# blinds_v60.net
KiCad netlist of a schematic drawn in EAGLE
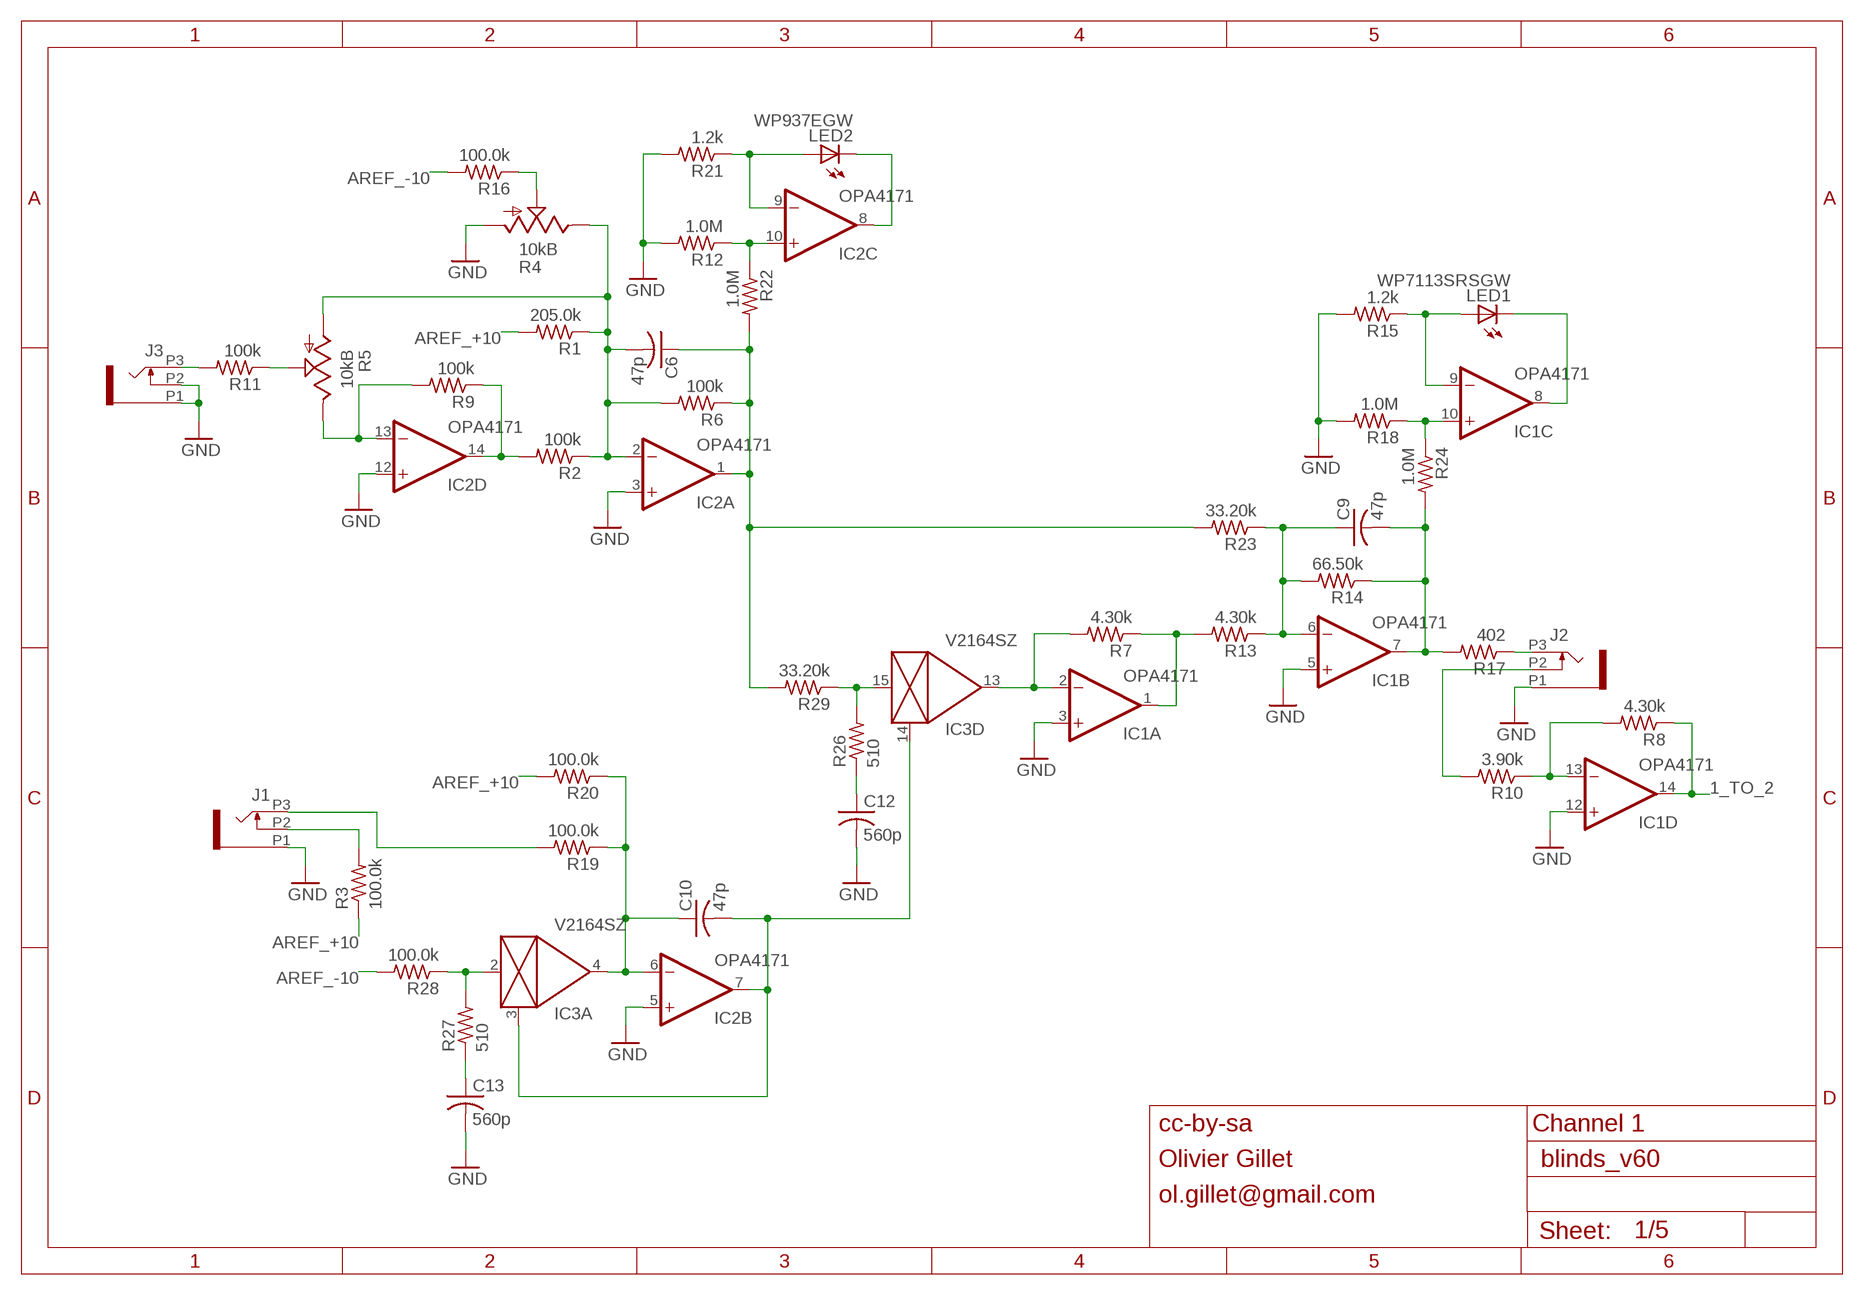
[diagram p0: schematic, sheet 1]
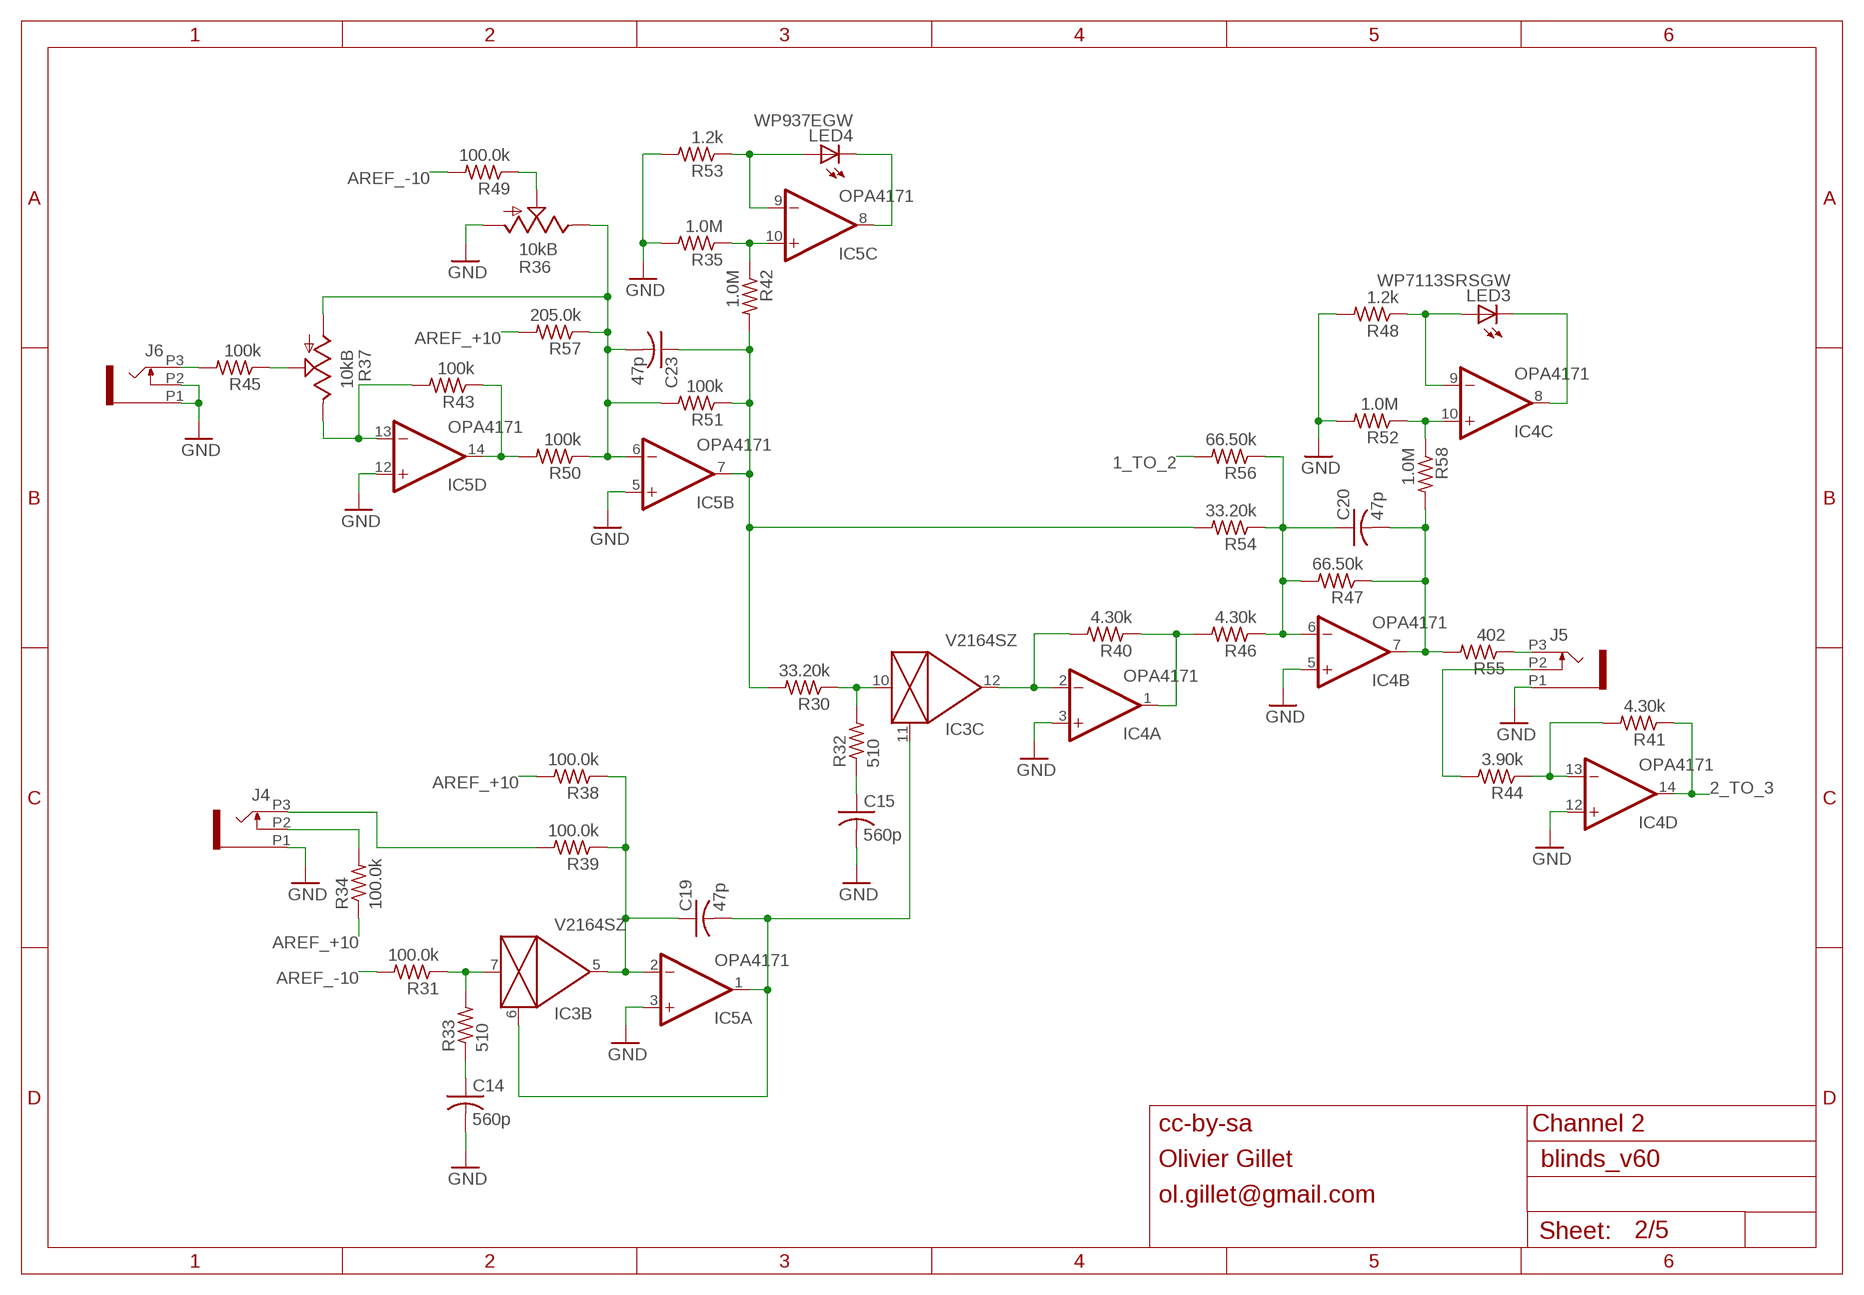
[diagram p1: schematic, sheet 2]
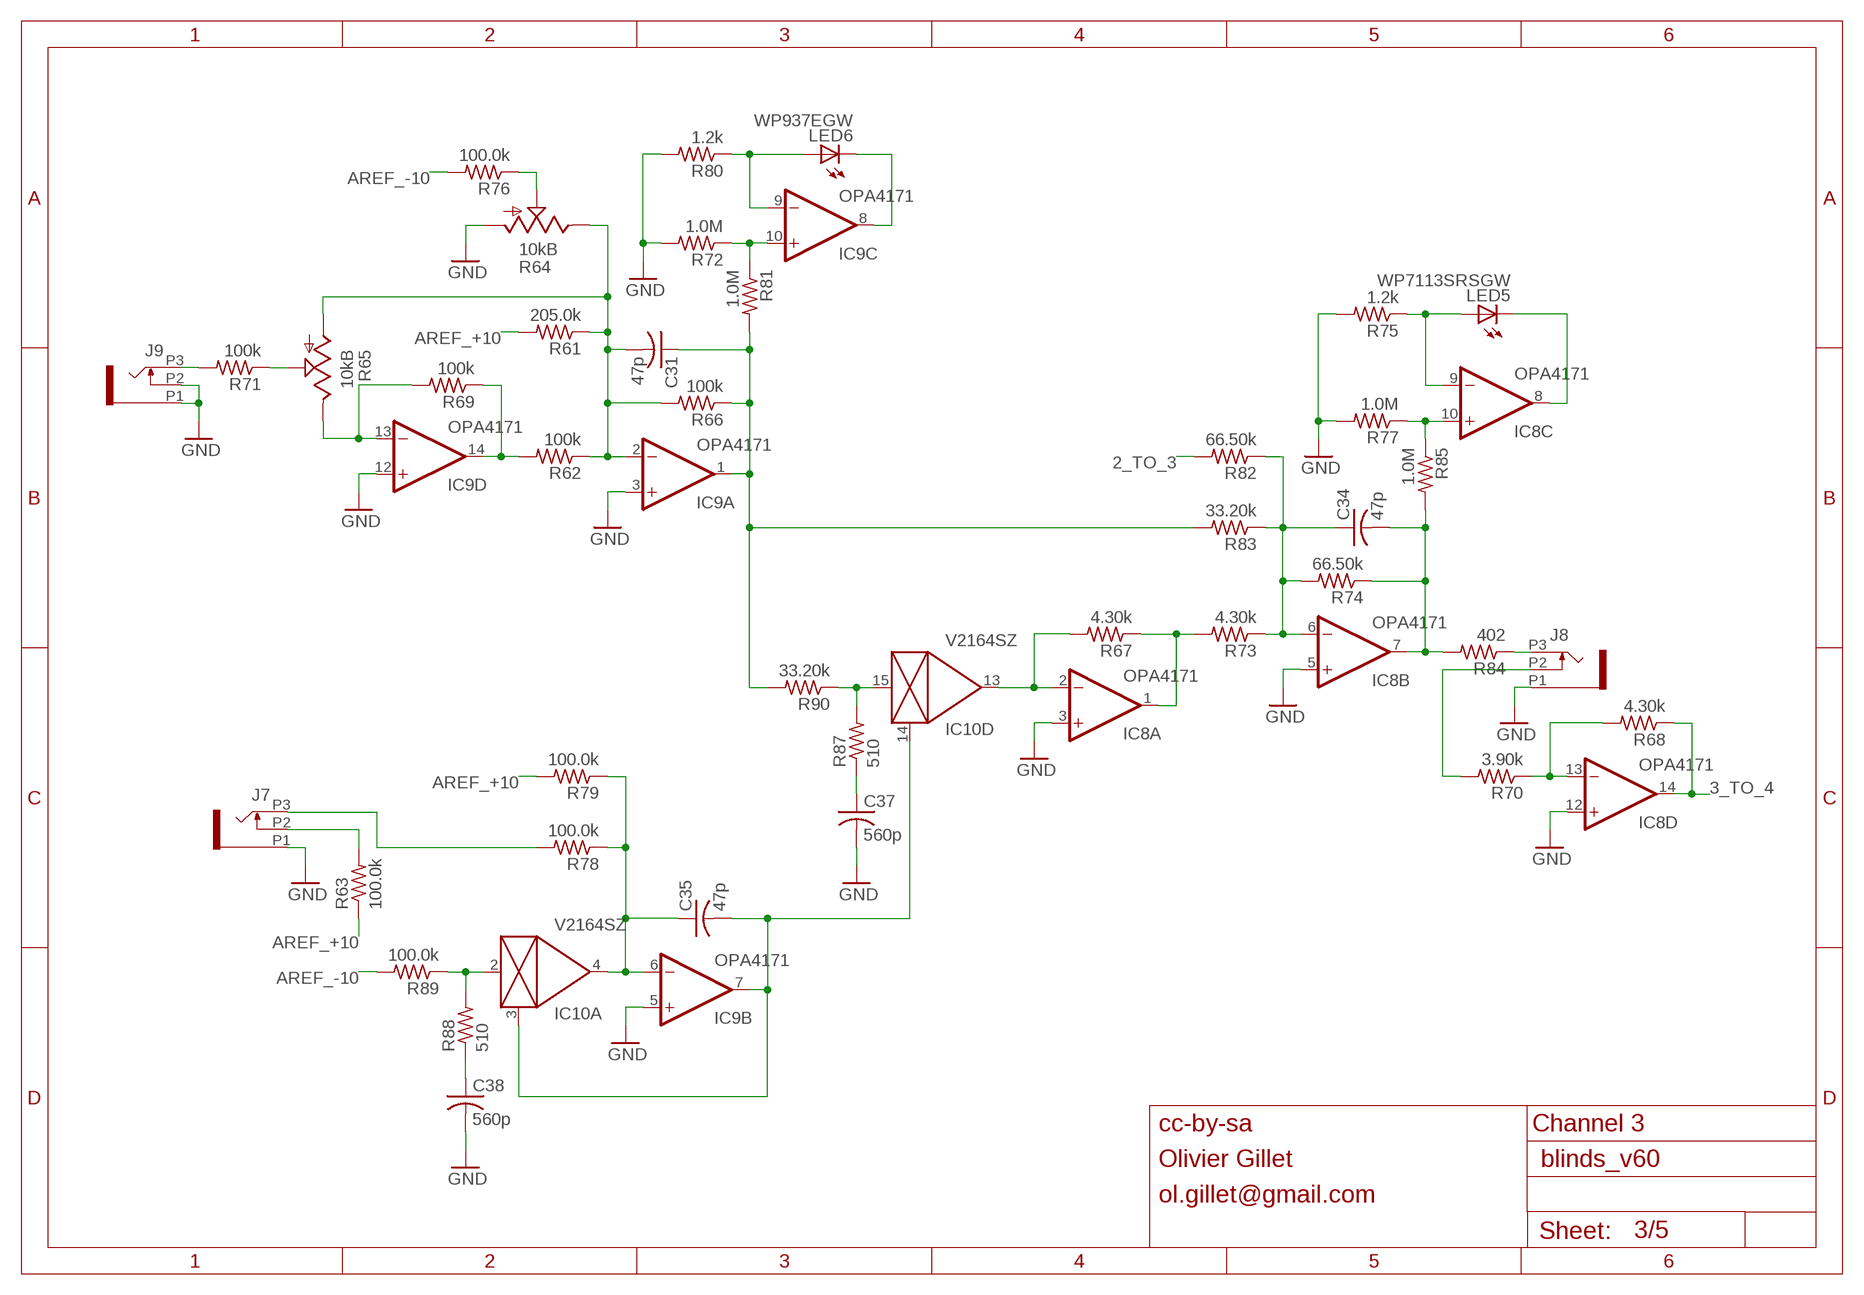
[diagram p2: schematic, sheet 3]
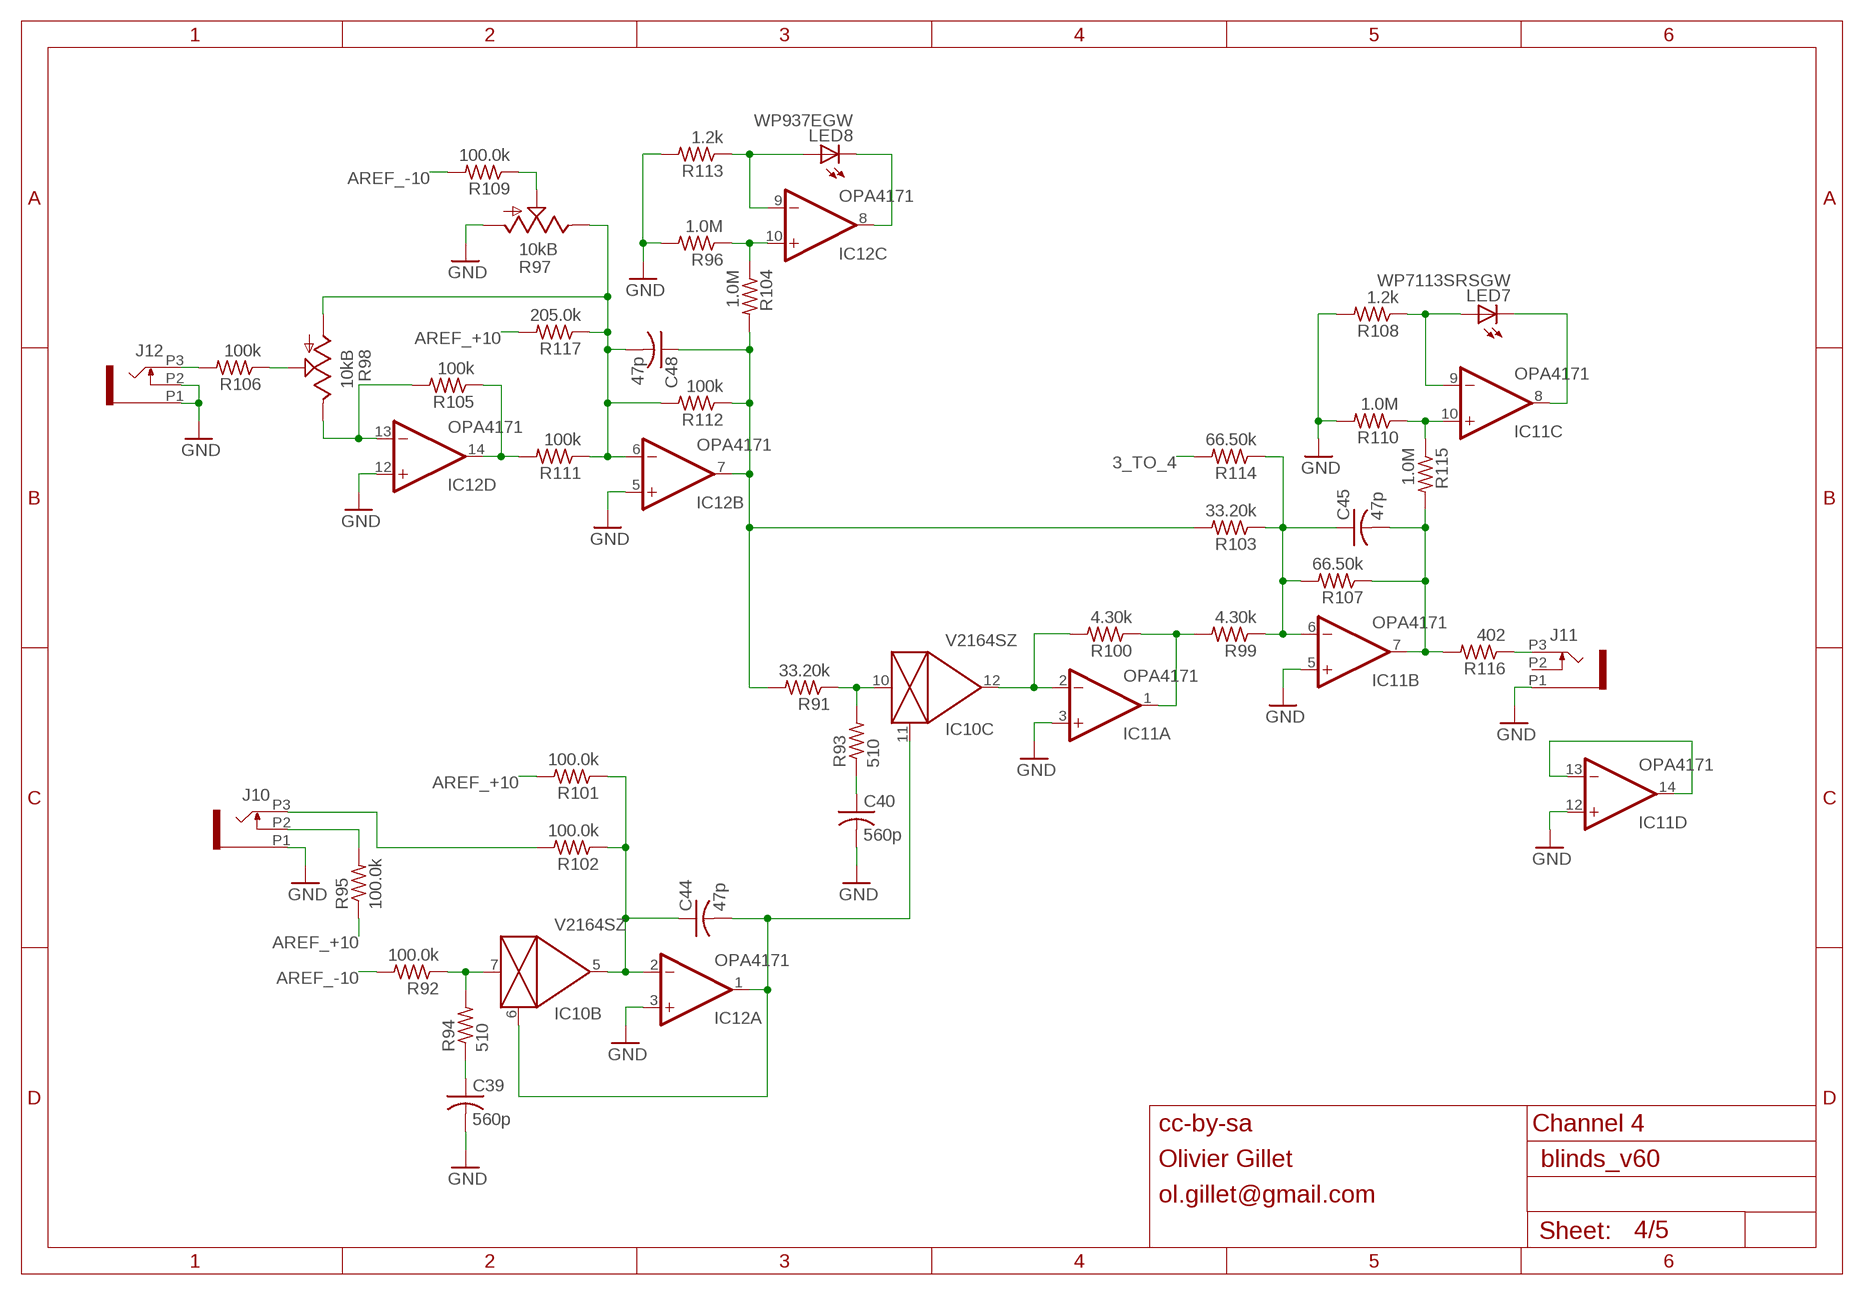
[diagram p3: schematic, sheet 4]
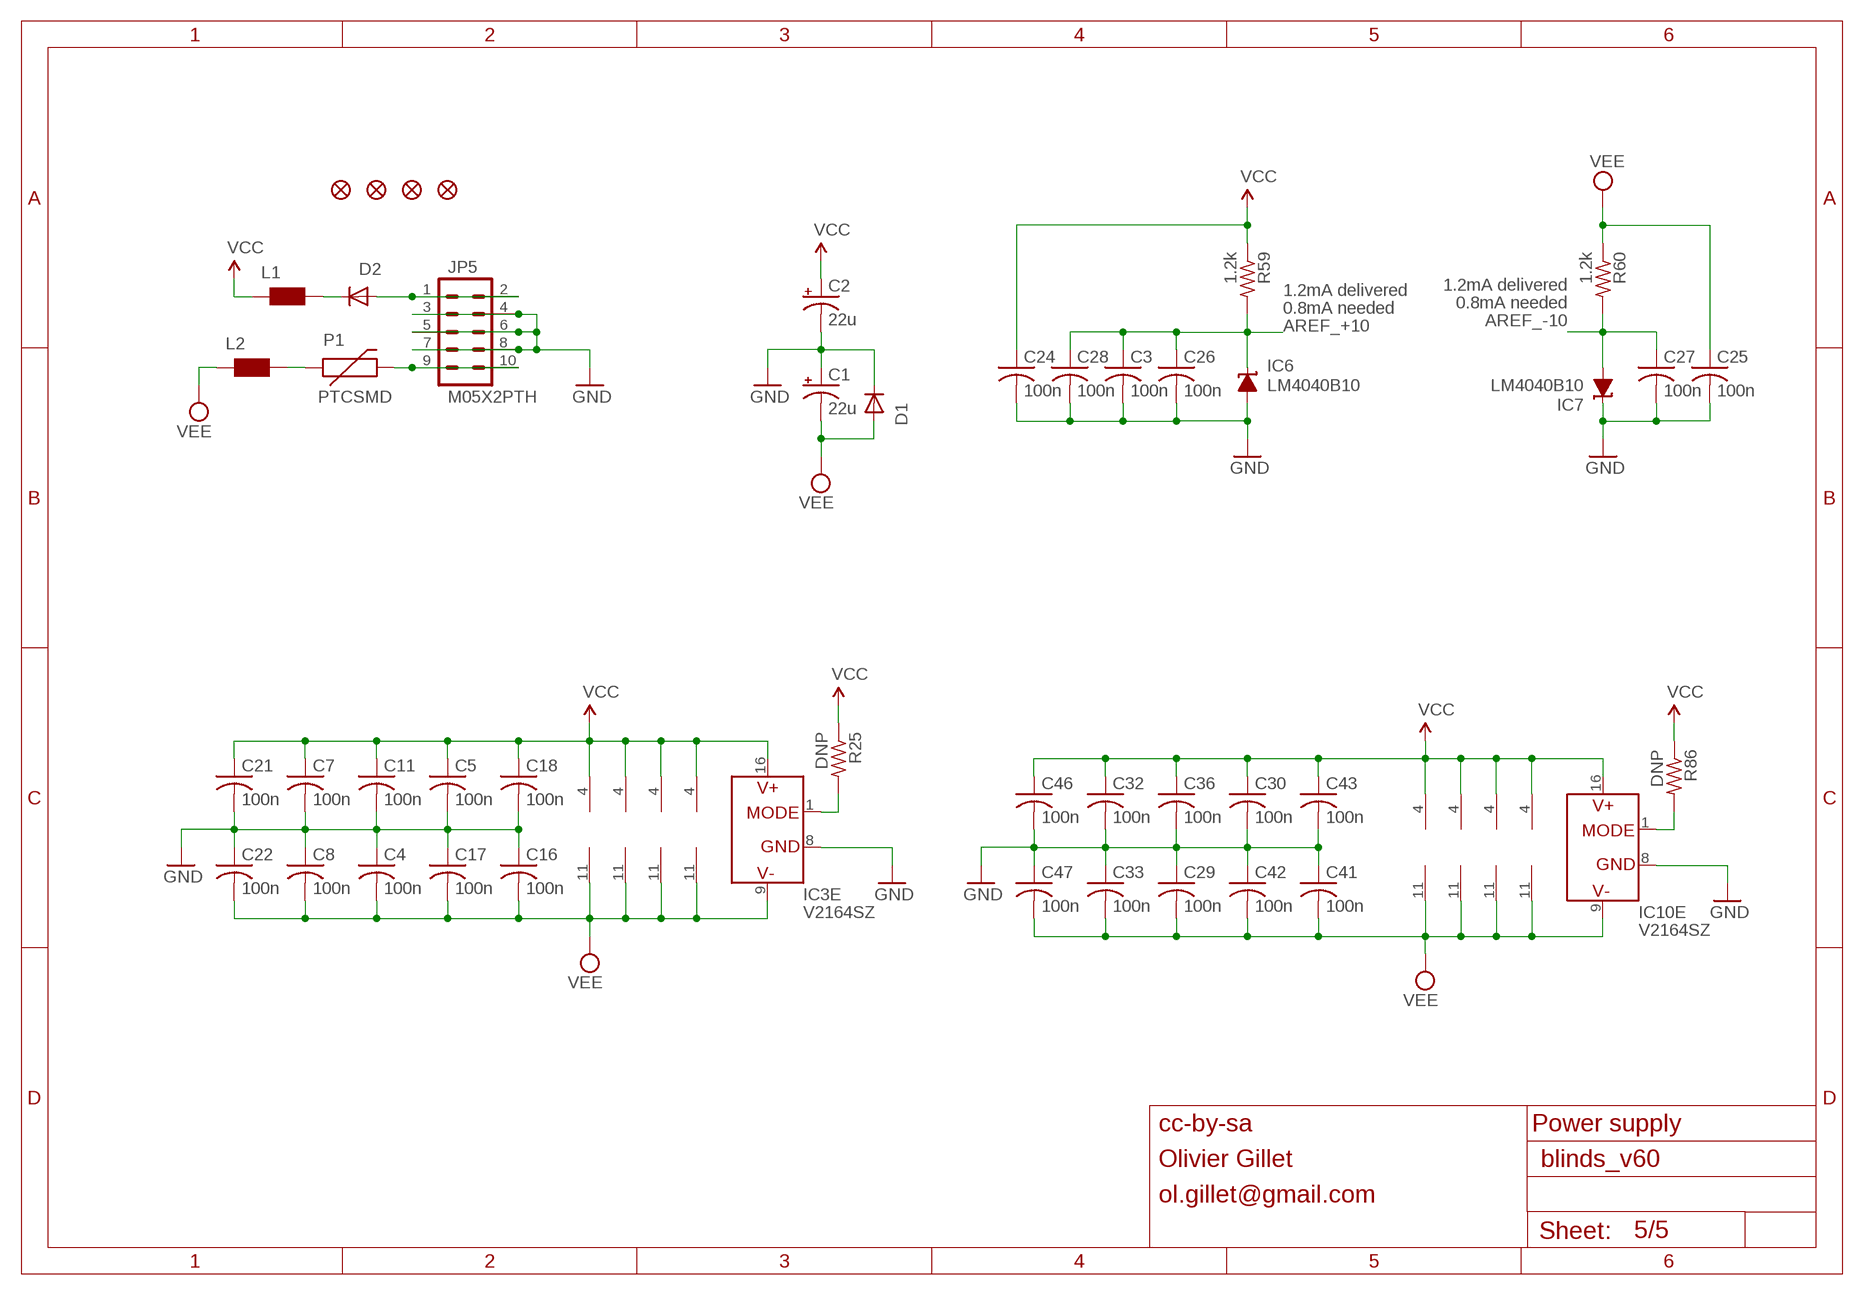
[diagram p4: schematic, sheet 5]

(export (version "E")
  (design (tool "Eeschema 10.0.6"))
  (components
    (comp (ref "C39")
      (value "560p")
      (footprint "eagle-import:C0603")
      (libsource (lib "eagle-import") (part "C-USC0603"))
    )
    (comp (ref "C40")
      (value "560p")
      (footprint "eagle-import:C0603")
      (libsource (lib "eagle-import") (part "C-USC0603"))
    )
    (comp (ref "C44")
      (value "47p")
      (footprint "eagle-import:C0603")
      (libsource (lib "eagle-import") (part "C-USC0603"))
    )
    (comp (ref "C45")
      (value "47p")
      (footprint "eagle-import:C0603")
      (libsource (lib "eagle-import") (part "C-USC0603"))
    )
    (comp (ref "C48")
      (value "47p")
      (footprint "eagle-import:C0603")
      (libsource (lib "eagle-import") (part "C-USC0603"))
    )
    (comp (ref "IC10")
      (value "V2164SZ")
      (footprint "eagle-import:SOIC16N")
      (libsource (lib "eagle-import") (part "SSM2164S"))
    )
    (comp (ref "IC11")
      (value "OPA4171")
      (footprint "eagle-import:TSSOP14")
      (libsource (lib "eagle-import") (part "TL074PW"))
    )
    (comp (ref "IC12")
      (value "OPA4171")
      (footprint "eagle-import:TSSOP14")
      (libsource (lib "eagle-import") (part "TL074PW"))
    )
    (comp (ref "J10")
      (value "PJ301_THONKICONN6")
      (footprint "eagle-import:WQP_PJ_301M6")
      (libsource (lib "eagle-import") (part "PJ301_THONKICONN6"))
    )
    (comp (ref "J11")
      (value "PJ301_THONKICONN6")
      (footprint "eagle-import:WQP_PJ_301M6")
      (libsource (lib "eagle-import") (part "PJ301_THONKICONN6"))
    )
    (comp (ref "J12")
      (value "PJ301_THONKICONN6")
      (footprint "eagle-import:WQP_PJ_301M6")
      (libsource (lib "eagle-import") (part "PJ301_THONKICONN6"))
    )
    (comp (ref "LED7")
      (value "WP7113SRSGW")
      (footprint "eagle-import:LED5MM")
      (libsource (lib "eagle-import") (part "LED5MM"))
    )
    (comp (ref "LED8")
      (value "WP937EGW")
      (footprint "eagle-import:LED3MM")
      (libsource (lib "eagle-import") (part "LED3MM"))
    )
    (comp (ref "R91")
      (value "33.20k")
      (footprint "eagle-import:R0603")
      (libsource (lib "eagle-import") (part "R-US_R0603"))
    )
    (comp (ref "R92")
      (value "100.0k")
      (footprint "eagle-import:R0603")
      (libsource (lib "eagle-import") (part "R-US_R0603"))
    )
    (comp (ref "R93")
      (value "510")
      (footprint "eagle-import:R0603")
      (libsource (lib "eagle-import") (part "R-US_R0603"))
    )
    (comp (ref "R94")
      (value "510")
      (footprint "eagle-import:R0603")
      (libsource (lib "eagle-import") (part "R-US_R0603"))
    )
    (comp (ref "R95")
      (value "100.0k")
      (footprint "eagle-import:R0603")
      (libsource (lib "eagle-import") (part "R-US_R0603"))
    )
    (comp (ref "R96")
      (value "1.0M")
      (footprint "eagle-import:R0603")
      (libsource (lib "eagle-import") (part "R-US_R0603"))
    )
    (comp (ref "R97")
      (value "10kB")
      (footprint "eagle-import:ALPS_POT_VERTICAL_PS")
      (libsource (lib "eagle-import") (part "POT_USVERTICAL_PS"))
    )
    (comp (ref "R98")
      (value "10kB")
      (footprint "eagle-import:ALPS_POT_VERTICAL")
      (libsource (lib "eagle-import") (part "POT_USVERTICAL"))
    )
    (comp (ref "R99")
      (value "4.30k")
      (footprint "eagle-import:R0603")
      (libsource (lib "eagle-import") (part "R-US_R0603"))
    )
    (comp (ref "R100")
      (value "4.30k")
      (footprint "eagle-import:R0603")
      (libsource (lib "eagle-import") (part "R-US_R0603"))
    )
    (comp (ref "R101")
      (value "100.0k")
      (footprint "eagle-import:R0603")
      (libsource (lib "eagle-import") (part "R-US_R0603"))
    )
    (comp (ref "R102")
      (value "100.0k")
      (footprint "eagle-import:R0603")
      (libsource (lib "eagle-import") (part "R-US_R0603"))
    )
    (comp (ref "R103")
      (value "33.20k")
      (footprint "eagle-import:R0603")
      (libsource (lib "eagle-import") (part "R-US_R0603"))
    )
    (comp (ref "R104")
      (value "1.0M")
      (footprint "eagle-import:R0603")
      (libsource (lib "eagle-import") (part "R-US_R0603"))
    )
    (comp (ref "R105")
      (value "100k")
      (footprint "eagle-import:R0603")
      (libsource (lib "eagle-import") (part "R-US_R0603"))
    )
    (comp (ref "R106")
      (value "100k")
      (footprint "eagle-import:R0603")
      (libsource (lib "eagle-import") (part "R-US_R0603"))
    )
    (comp (ref "R107")
      (value "66.50k")
      (footprint "eagle-import:R0603")
      (libsource (lib "eagle-import") (part "R-US_R0603"))
    )
    (comp (ref "R108")
      (value "1.2k")
      (footprint "eagle-import:R0603")
      (libsource (lib "eagle-import") (part "R-US_R0603"))
    )
    (comp (ref "R109")
      (value "100.0k")
      (footprint "eagle-import:R0603")
      (libsource (lib "eagle-import") (part "R-US_R0603"))
    )
    (comp (ref "R110")
      (value "1.0M")
      (footprint "eagle-import:R0603")
      (libsource (lib "eagle-import") (part "R-US_R0603"))
    )
    (comp (ref "R111")
      (value "100k")
      (footprint "eagle-import:R0603")
      (libsource (lib "eagle-import") (part "R-US_R0603"))
    )
    (comp (ref "R112")
      (value "100k")
      (footprint "eagle-import:R0603")
      (libsource (lib "eagle-import") (part "R-US_R0603"))
    )
    (comp (ref "R113")
      (value "1.2k")
      (footprint "eagle-import:R0603")
      (libsource (lib "eagle-import") (part "R-US_R0603"))
    )
    (comp (ref "R114")
      (value "66.50k")
      (footprint "eagle-import:R0603")
      (libsource (lib "eagle-import") (part "R-US_R0603"))
    )
    (comp (ref "R115")
      (value "1.0M")
      (footprint "eagle-import:R0603")
      (libsource (lib "eagle-import") (part "R-US_R0603"))
    )
    (comp (ref "R116")
      (value "402")
      (footprint "eagle-import:R0603")
      (libsource (lib "eagle-import") (part "R-US_R0603"))
    )
    (comp (ref "R117")
      (value "205.0k")
      (footprint "eagle-import:R0603")
      (libsource (lib "eagle-import") (part "R-US_R0603"))
    )
    (comp (ref "C1")
      (value "22u")
      (footprint "eagle-import:PANASONIC_C")
      (libsource (lib "eagle-import") (part "CPOL-USC"))
    )
    (comp (ref "C2")
      (value "22u")
      (footprint "eagle-import:PANASONIC_C")
      (libsource (lib "eagle-import") (part "CPOL-USC"))
    )
    (comp (ref "C3")
      (value "100n")
      (footprint "eagle-import:C0603")
      (libsource (lib "eagle-import") (part "C-USC0603"))
    )
    (comp (ref "C4")
      (value "100n")
      (footprint "eagle-import:C0603")
      (libsource (lib "eagle-import") (part "C-USC0603"))
    )
    (comp (ref "C5")
      (value "100n")
      (footprint "eagle-import:C0603")
      (libsource (lib "eagle-import") (part "C-USC0603"))
    )
    (comp (ref "C7")
      (value "100n")
      (footprint "eagle-import:C0603")
      (libsource (lib "eagle-import") (part "C-USC0603"))
    )
    (comp (ref "C8")
      (value "100n")
      (footprint "eagle-import:C0603")
      (libsource (lib "eagle-import") (part "C-USC0603"))
    )
    (comp (ref "C11")
      (value "100n")
      (footprint "eagle-import:C0603")
      (libsource (lib "eagle-import") (part "C-USC0603"))
    )
    (comp (ref "C16")
      (value "100n")
      (footprint "eagle-import:C0603")
      (libsource (lib "eagle-import") (part "C-USC0603"))
    )
    (comp (ref "C17")
      (value "100n")
      (footprint "eagle-import:C0603")
      (libsource (lib "eagle-import") (part "C-USC0603"))
    )
    (comp (ref "C18")
      (value "100n")
      (footprint "eagle-import:C0603")
      (libsource (lib "eagle-import") (part "C-USC0603"))
    )
    (comp (ref "C21")
      (value "100n")
      (footprint "eagle-import:C0603")
      (libsource (lib "eagle-import") (part "C-USC0603"))
    )
    (comp (ref "C22")
      (value "100n")
      (footprint "eagle-import:C0603")
      (libsource (lib "eagle-import") (part "C-USC0603"))
    )
    (comp (ref "C24")
      (value "100n")
      (footprint "eagle-import:C0603")
      (libsource (lib "eagle-import") (part "C-USC0603"))
    )
    (comp (ref "C25")
      (value "100n")
      (footprint "eagle-import:C0603")
      (libsource (lib "eagle-import") (part "C-USC0603"))
    )
    (comp (ref "C26")
      (value "100n")
      (footprint "eagle-import:C0603")
      (libsource (lib "eagle-import") (part "C-USC0603"))
    )
    (comp (ref "C27")
      (value "100n")
      (footprint "eagle-import:C0603")
      (libsource (lib "eagle-import") (part "C-USC0603"))
    )
    (comp (ref "C28")
      (value "100n")
      (footprint "eagle-import:C0603")
      (libsource (lib "eagle-import") (part "C-USC0603"))
    )
    (comp (ref "C29")
      (value "100n")
      (footprint "eagle-import:C0603")
      (libsource (lib "eagle-import") (part "C-USC0603"))
    )
    (comp (ref "C30")
      (value "100n")
      (footprint "eagle-import:C0603")
      (libsource (lib "eagle-import") (part "C-USC0603"))
    )
    (comp (ref "C32")
      (value "100n")
      (footprint "eagle-import:C0603")
      (libsource (lib "eagle-import") (part "C-USC0603"))
    )
    (comp (ref "C33")
      (value "100n")
      (footprint "eagle-import:C0603")
      (libsource (lib "eagle-import") (part "C-USC0603"))
    )
    (comp (ref "C36")
      (value "100n")
      (footprint "eagle-import:C0603")
      (libsource (lib "eagle-import") (part "C-USC0603"))
    )
    (comp (ref "C41")
      (value "100n")
      (footprint "eagle-import:C0603")
      (libsource (lib "eagle-import") (part "C-USC0603"))
    )
    (comp (ref "C42")
      (value "100n")
      (footprint "eagle-import:C0603")
      (libsource (lib "eagle-import") (part "C-USC0603"))
    )
    (comp (ref "C43")
      (value "100n")
      (footprint "eagle-import:C0603")
      (libsource (lib "eagle-import") (part "C-USC0603"))
    )
    (comp (ref "C46")
      (value "100n")
      (footprint "eagle-import:C0603")
      (libsource (lib "eagle-import") (part "C-USC0603"))
    )
    (comp (ref "C47")
      (value "100n")
      (footprint "eagle-import:C0603")
      (libsource (lib "eagle-import") (part "C-USC0603"))
    )
    (comp (ref "D1")
      (value "1N5819HW")
      (footprint "eagle-import:SOD123")
      (libsource (lib "eagle-import") (part "DIODE-SOD123"))
    )
    (comp (ref "D2")
      (value "1N5819HW")
      (footprint "eagle-import:SOD123")
      (libsource (lib "eagle-import") (part "DIODE-SOD123"))
    )
    (comp (ref "IC1")
      (value "OPA4171")
      (footprint "eagle-import:TSSOP14")
      (libsource (lib "eagle-import") (part "TL074PW"))
    )
    (comp (ref "IC2")
      (value "OPA4171")
      (footprint "eagle-import:TSSOP14")
      (libsource (lib "eagle-import") (part "TL074PW"))
    )
    (comp (ref "IC3")
      (value "V2164SZ")
      (footprint "eagle-import:SOIC16N")
      (libsource (lib "eagle-import") (part "SSM2164S"))
    )
    (comp (ref "IC4")
      (value "OPA4171")
      (footprint "eagle-import:TSSOP14")
      (libsource (lib "eagle-import") (part "TL074PW"))
    )
    (comp (ref "IC5")
      (value "OPA4171")
      (footprint "eagle-import:TSSOP14")
      (libsource (lib "eagle-import") (part "TL074PW"))
    )
    (comp (ref "IC6")
      (value "LM4040B10")
      (footprint "eagle-import:DBZ_R-PDSO-G3")
      (libsource (lib "eagle-import") (part "LM4041DBZB12"))
    )
    (comp (ref "IC7")
      (value "LM4040B10")
      (footprint "eagle-import:DBZ_R-PDSO-G3")
      (libsource (lib "eagle-import") (part "LM4041DBZB12"))
    )
    (comp (ref "IC8")
      (value "OPA4171")
      (footprint "eagle-import:TSSOP14")
      (libsource (lib "eagle-import") (part "TL074PW"))
    )
    (comp (ref "IC9")
      (value "OPA4171")
      (footprint "eagle-import:TSSOP14")
      (libsource (lib "eagle-import") (part "TL074PW"))
    )
    (comp (ref "JP1")
      (value "FIDUCIAL1X2")
      (footprint "eagle-import:FIDUCIAL-1X2")
      (libsource (lib "eagle-import") (part "FIDUCIAL1X2"))
    )
    (comp (ref "JP2")
      (value "FIDUCIAL1X2")
      (footprint "eagle-import:FIDUCIAL-1X2")
      (libsource (lib "eagle-import") (part "FIDUCIAL1X2"))
    )
    (comp (ref "JP3")
      (value "FIDUCIAL1X2")
      (footprint "eagle-import:FIDUCIAL-1X2")
      (libsource (lib "eagle-import") (part "FIDUCIAL1X2"))
    )
    (comp (ref "JP4")
      (value "FIDUCIAL1X2")
      (footprint "eagle-import:FIDUCIAL-1X2")
      (libsource (lib "eagle-import") (part "FIDUCIAL1X2"))
    )
    (comp (ref "JP5")
      (value "M05X2PTH")
      (footprint "eagle-import:AVR_ICSP")
      (libsource (lib "eagle-import") (part "M05X2PTH"))
    )
    (comp (ref "L1")
      (value "WE-CBF_0603")
      (footprint "eagle-import:0603")
      (libsource (lib "eagle-import") (part "WE-CBF_0603"))
    )
    (comp (ref "L2")
      (value "WE-CBF_0603")
      (footprint "eagle-import:0603")
      (libsource (lib "eagle-import") (part "WE-CBF_0603"))
    )
    (comp (ref "P1")
      (value "PTCSMD")
      (footprint "eagle-import:PTC-1206")
      (libsource (lib "eagle-import") (part "PTCSMD"))
    )
    (comp (ref "R25")
      (value "DNP")
      (footprint "eagle-import:R0603")
      (libsource (lib "eagle-import") (part "R-US_R0603"))
    )
    (comp (ref "R59")
      (value "1.2k")
      (footprint "eagle-import:R0603")
      (libsource (lib "eagle-import") (part "R-US_R0603"))
    )
    (comp (ref "R60")
      (value "1.2k")
      (footprint "eagle-import:R0603")
      (libsource (lib "eagle-import") (part "R-US_R0603"))
    )
    (comp (ref "R86")
      (value "DNP")
      (footprint "eagle-import:R0603")
      (libsource (lib "eagle-import") (part "R-US_R0603"))
    )
    (comp (ref "C14")
      (value "560p")
      (footprint "eagle-import:C0603")
      (libsource (lib "eagle-import") (part "C-USC0603"))
    )
    (comp (ref "C15")
      (value "560p")
      (footprint "eagle-import:C0603")
      (libsource (lib "eagle-import") (part "C-USC0603"))
    )
    (comp (ref "C19")
      (value "47p")
      (footprint "eagle-import:C0603")
      (libsource (lib "eagle-import") (part "C-USC0603"))
    )
    (comp (ref "C20")
      (value "47p")
      (footprint "eagle-import:C0603")
      (libsource (lib "eagle-import") (part "C-USC0603"))
    )
    (comp (ref "C23")
      (value "47p")
      (footprint "eagle-import:C0603")
      (libsource (lib "eagle-import") (part "C-USC0603"))
    )
    (comp (ref "J4")
      (value "PJ301_THONKICONN6")
      (footprint "eagle-import:WQP_PJ_301M6")
      (libsource (lib "eagle-import") (part "PJ301_THONKICONN6"))
    )
    (comp (ref "J5")
      (value "PJ301_THONKICONN6")
      (footprint "eagle-import:WQP_PJ_301M6")
      (libsource (lib "eagle-import") (part "PJ301_THONKICONN6"))
    )
    (comp (ref "J6")
      (value "PJ301_THONKICONN6")
      (footprint "eagle-import:WQP_PJ_301M6")
      (libsource (lib "eagle-import") (part "PJ301_THONKICONN6"))
    )
    (comp (ref "LED3")
      (value "WP7113SRSGW")
      (footprint "eagle-import:LED5MM")
      (libsource (lib "eagle-import") (part "LED5MM"))
    )
    (comp (ref "LED4")
      (value "WP937EGW")
      (footprint "eagle-import:LED3MM")
      (libsource (lib "eagle-import") (part "LED3MM"))
    )
    (comp (ref "R30")
      (value "33.20k")
      (footprint "eagle-import:R0603")
      (libsource (lib "eagle-import") (part "R-US_R0603"))
    )
    (comp (ref "R31")
      (value "100.0k")
      (footprint "eagle-import:R0603")
      (libsource (lib "eagle-import") (part "R-US_R0603"))
    )
    (comp (ref "R32")
      (value "510")
      (footprint "eagle-import:R0603")
      (libsource (lib "eagle-import") (part "R-US_R0603"))
    )
    (comp (ref "R33")
      (value "510")
      (footprint "eagle-import:R0603")
      (libsource (lib "eagle-import") (part "R-US_R0603"))
    )
    (comp (ref "R34")
      (value "100.0k")
      (footprint "eagle-import:R0603")
      (libsource (lib "eagle-import") (part "R-US_R0603"))
    )
    (comp (ref "R35")
      (value "1.0M")
      (footprint "eagle-import:R0603")
      (libsource (lib "eagle-import") (part "R-US_R0603"))
    )
    (comp (ref "R36")
      (value "10kB")
      (footprint "eagle-import:ALPS_POT_VERTICAL_PS")
      (libsource (lib "eagle-import") (part "POT_USVERTICAL_PS"))
    )
    (comp (ref "R37")
      (value "10kB")
      (footprint "eagle-import:ALPS_POT_VERTICAL")
      (libsource (lib "eagle-import") (part "POT_USVERTICAL"))
    )
    (comp (ref "R38")
      (value "100.0k")
      (footprint "eagle-import:R0603")
      (libsource (lib "eagle-import") (part "R-US_R0603"))
    )
    (comp (ref "R39")
      (value "100.0k")
      (footprint "eagle-import:R0603")
      (libsource (lib "eagle-import") (part "R-US_R0603"))
    )
    (comp (ref "R40")
      (value "4.30k")
      (footprint "eagle-import:R0603")
      (libsource (lib "eagle-import") (part "R-US_R0603"))
    )
    (comp (ref "R41")
      (value "4.30k")
      (footprint "eagle-import:R0603")
      (libsource (lib "eagle-import") (part "R-US_R0603"))
    )
    (comp (ref "R42")
      (value "1.0M")
      (footprint "eagle-import:R0603")
      (libsource (lib "eagle-import") (part "R-US_R0603"))
    )
    (comp (ref "R43")
      (value "100k")
      (footprint "eagle-import:R0603")
      (libsource (lib "eagle-import") (part "R-US_R0603"))
    )
    (comp (ref "R44")
      (value "3.90k")
      (footprint "eagle-import:R0603")
      (libsource (lib "eagle-import") (part "R-US_R0603"))
    )
    (comp (ref "R45")
      (value "100k")
      (footprint "eagle-import:R0603")
      (libsource (lib "eagle-import") (part "R-US_R0603"))
    )
    (comp (ref "R46")
      (value "4.30k")
      (footprint "eagle-import:R0603")
      (libsource (lib "eagle-import") (part "R-US_R0603"))
    )
    (comp (ref "R47")
      (value "66.50k")
      (footprint "eagle-import:R0603")
      (libsource (lib "eagle-import") (part "R-US_R0603"))
    )
    (comp (ref "R48")
      (value "1.2k")
      (footprint "eagle-import:R0603")
      (libsource (lib "eagle-import") (part "R-US_R0603"))
    )
    (comp (ref "R49")
      (value "100.0k")
      (footprint "eagle-import:R0603")
      (libsource (lib "eagle-import") (part "R-US_R0603"))
    )
    (comp (ref "R50")
      (value "100k")
      (footprint "eagle-import:R0603")
      (libsource (lib "eagle-import") (part "R-US_R0603"))
    )
    (comp (ref "R51")
      (value "100k")
      (footprint "eagle-import:R0603")
      (libsource (lib "eagle-import") (part "R-US_R0603"))
    )
    (comp (ref "R52")
      (value "1.0M")
      (footprint "eagle-import:R0603")
      (libsource (lib "eagle-import") (part "R-US_R0603"))
    )
    (comp (ref "R53")
      (value "1.2k")
      (footprint "eagle-import:R0603")
      (libsource (lib "eagle-import") (part "R-US_R0603"))
    )
    (comp (ref "R54")
      (value "33.20k")
      (footprint "eagle-import:R0603")
      (libsource (lib "eagle-import") (part "R-US_R0603"))
    )
    (comp (ref "R55")
      (value "402")
      (footprint "eagle-import:R0603")
      (libsource (lib "eagle-import") (part "R-US_R0603"))
    )
    (comp (ref "R56")
      (value "66.50k")
      (footprint "eagle-import:R0603")
      (libsource (lib "eagle-import") (part "R-US_R0603"))
    )
    (comp (ref "R57")
      (value "205.0k")
      (footprint "eagle-import:R0603")
      (libsource (lib "eagle-import") (part "R-US_R0603"))
    )
    (comp (ref "R58")
      (value "1.0M")
      (footprint "eagle-import:R0603")
      (libsource (lib "eagle-import") (part "R-US_R0603"))
    )
    (comp (ref "C6")
      (value "47p")
      (footprint "eagle-import:C0603")
      (libsource (lib "eagle-import") (part "C-USC0603"))
    )
    (comp (ref "C9")
      (value "47p")
      (footprint "eagle-import:C0603")
      (libsource (lib "eagle-import") (part "C-USC0603"))
    )
    (comp (ref "C10")
      (value "47p")
      (footprint "eagle-import:C0603")
      (libsource (lib "eagle-import") (part "C-USC0603"))
    )
    (comp (ref "C12")
      (value "560p")
      (footprint "eagle-import:C0603")
      (libsource (lib "eagle-import") (part "C-USC0603"))
    )
    (comp (ref "C13")
      (value "560p")
      (footprint "eagle-import:C0603")
      (libsource (lib "eagle-import") (part "C-USC0603"))
    )
    (comp (ref "J1")
      (value "PJ301_THONKICONN6")
      (footprint "eagle-import:WQP_PJ_301M6")
      (libsource (lib "eagle-import") (part "PJ301_THONKICONN6"))
    )
    (comp (ref "J2")
      (value "PJ301_THONKICONN6")
      (footprint "eagle-import:WQP_PJ_301M6")
      (libsource (lib "eagle-import") (part "PJ301_THONKICONN6"))
    )
    (comp (ref "J3")
      (value "PJ301_THONKICONN6")
      (footprint "eagle-import:WQP_PJ_301M6")
      (libsource (lib "eagle-import") (part "PJ301_THONKICONN6"))
    )
    (comp (ref "LED1")
      (value "WP7113SRSGW")
      (footprint "eagle-import:LED5MM")
      (libsource (lib "eagle-import") (part "LED5MM"))
    )
    (comp (ref "LED2")
      (value "WP937EGW")
      (footprint "eagle-import:LED3MM")
      (libsource (lib "eagle-import") (part "LED3MM"))
    )
    (comp (ref "R1")
      (value "205.0k")
      (footprint "eagle-import:R0603")
      (libsource (lib "eagle-import") (part "R-US_R0603"))
    )
    (comp (ref "R2")
      (value "100k")
      (footprint "eagle-import:R0603")
      (libsource (lib "eagle-import") (part "R-US_R0603"))
    )
    (comp (ref "R3")
      (value "100.0k")
      (footprint "eagle-import:R0603")
      (libsource (lib "eagle-import") (part "R-US_R0603"))
    )
    (comp (ref "R4")
      (value "10kB")
      (footprint "eagle-import:ALPS_POT_VERTICAL_PS")
      (libsource (lib "eagle-import") (part "POT_USVERTICAL_PS"))
    )
    (comp (ref "R5")
      (value "10kB")
      (footprint "eagle-import:ALPS_POT_VERTICAL")
      (libsource (lib "eagle-import") (part "POT_USVERTICAL"))
    )
    (comp (ref "R6")
      (value "100k")
      (footprint "eagle-import:R0603")
      (libsource (lib "eagle-import") (part "R-US_R0603"))
    )
    (comp (ref "R7")
      (value "4.30k")
      (footprint "eagle-import:R0603")
      (libsource (lib "eagle-import") (part "R-US_R0603"))
    )
    (comp (ref "R8")
      (value "4.30k")
      (footprint "eagle-import:R0603")
      (libsource (lib "eagle-import") (part "R-US_R0603"))
    )
    (comp (ref "R9")
      (value "100k")
      (footprint "eagle-import:R0603")
      (libsource (lib "eagle-import") (part "R-US_R0603"))
    )
    (comp (ref "R10")
      (value "3.90k")
      (footprint "eagle-import:R0603")
      (libsource (lib "eagle-import") (part "R-US_R0603"))
    )
    (comp (ref "R11")
      (value "100k")
      (footprint "eagle-import:R0603")
      (libsource (lib "eagle-import") (part "R-US_R0603"))
    )
    (comp (ref "R12")
      (value "1.0M")
      (footprint "eagle-import:R0603")
      (libsource (lib "eagle-import") (part "R-US_R0603"))
    )
    (comp (ref "R13")
      (value "4.30k")
      (footprint "eagle-import:R0603")
      (libsource (lib "eagle-import") (part "R-US_R0603"))
    )
    (comp (ref "R14")
      (value "66.50k")
      (footprint "eagle-import:R0603")
      (libsource (lib "eagle-import") (part "R-US_R0603"))
    )
    (comp (ref "R15")
      (value "1.2k")
      (footprint "eagle-import:R0603")
      (libsource (lib "eagle-import") (part "R-US_R0603"))
    )
    (comp (ref "R16")
      (value "100.0k")
      (footprint "eagle-import:R0603")
      (libsource (lib "eagle-import") (part "R-US_R0603"))
    )
    (comp (ref "R17")
      (value "402")
      (footprint "eagle-import:R0603")
      (libsource (lib "eagle-import") (part "R-US_R0603"))
    )
    (comp (ref "R18")
      (value "1.0M")
      (footprint "eagle-import:R0603")
      (libsource (lib "eagle-import") (part "R-US_R0603"))
    )
    (comp (ref "R19")
      (value "100.0k")
      (footprint "eagle-import:R0603")
      (libsource (lib "eagle-import") (part "R-US_R0603"))
    )
    (comp (ref "R20")
      (value "100.0k")
      (footprint "eagle-import:R0603")
      (libsource (lib "eagle-import") (part "R-US_R0603"))
    )
    (comp (ref "R21")
      (value "1.2k")
      (footprint "eagle-import:R0603")
      (libsource (lib "eagle-import") (part "R-US_R0603"))
    )
    (comp (ref "R22")
      (value "1.0M")
      (footprint "eagle-import:R0603")
      (libsource (lib "eagle-import") (part "R-US_R0603"))
    )
    (comp (ref "R23")
      (value "33.20k")
      (footprint "eagle-import:R0603")
      (libsource (lib "eagle-import") (part "R-US_R0603"))
    )
    (comp (ref "R24")
      (value "1.0M")
      (footprint "eagle-import:R0603")
      (libsource (lib "eagle-import") (part "R-US_R0603"))
    )
    (comp (ref "R26")
      (value "510")
      (footprint "eagle-import:R0603")
      (libsource (lib "eagle-import") (part "R-US_R0603"))
    )
    (comp (ref "R27")
      (value "510")
      (footprint "eagle-import:R0603")
      (libsource (lib "eagle-import") (part "R-US_R0603"))
    )
    (comp (ref "R28")
      (value "100.0k")
      (footprint "eagle-import:R0603")
      (libsource (lib "eagle-import") (part "R-US_R0603"))
    )
    (comp (ref "R29")
      (value "33.20k")
      (footprint "eagle-import:R0603")
      (libsource (lib "eagle-import") (part "R-US_R0603"))
    )
    (comp (ref "C31")
      (value "47p")
      (footprint "eagle-import:C0603")
      (libsource (lib "eagle-import") (part "C-USC0603"))
    )
    (comp (ref "C34")
      (value "47p")
      (footprint "eagle-import:C0603")
      (libsource (lib "eagle-import") (part "C-USC0603"))
    )
    (comp (ref "C35")
      (value "47p")
      (footprint "eagle-import:C0603")
      (libsource (lib "eagle-import") (part "C-USC0603"))
    )
    (comp (ref "C37")
      (value "560p")
      (footprint "eagle-import:C0603")
      (libsource (lib "eagle-import") (part "C-USC0603"))
    )
    (comp (ref "C38")
      (value "560p")
      (footprint "eagle-import:C0603")
      (libsource (lib "eagle-import") (part "C-USC0603"))
    )
    (comp (ref "J7")
      (value "PJ301_THONKICONN6")
      (footprint "eagle-import:WQP_PJ_301M6")
      (libsource (lib "eagle-import") (part "PJ301_THONKICONN6"))
    )
    (comp (ref "J8")
      (value "PJ301_THONKICONN6")
      (footprint "eagle-import:WQP_PJ_301M6")
      (libsource (lib "eagle-import") (part "PJ301_THONKICONN6"))
    )
    (comp (ref "J9")
      (value "PJ301_THONKICONN6")
      (footprint "eagle-import:WQP_PJ_301M6")
      (libsource (lib "eagle-import") (part "PJ301_THONKICONN6"))
    )
    (comp (ref "LED5")
      (value "WP7113SRSGW")
      (footprint "eagle-import:LED5MM")
      (libsource (lib "eagle-import") (part "LED5MM"))
    )
    (comp (ref "LED6")
      (value "WP937EGW")
      (footprint "eagle-import:LED3MM")
      (libsource (lib "eagle-import") (part "LED3MM"))
    )
    (comp (ref "R61")
      (value "205.0k")
      (footprint "eagle-import:R0603")
      (libsource (lib "eagle-import") (part "R-US_R0603"))
    )
    (comp (ref "R62")
      (value "100k")
      (footprint "eagle-import:R0603")
      (libsource (lib "eagle-import") (part "R-US_R0603"))
    )
    (comp (ref "R63")
      (value "100.0k")
      (footprint "eagle-import:R0603")
      (libsource (lib "eagle-import") (part "R-US_R0603"))
    )
    (comp (ref "R64")
      (value "10kB")
      (footprint "eagle-import:ALPS_POT_VERTICAL_PS")
      (libsource (lib "eagle-import") (part "POT_USVERTICAL_PS"))
    )
    (comp (ref "R65")
      (value "10kB")
      (footprint "eagle-import:ALPS_POT_VERTICAL")
      (libsource (lib "eagle-import") (part "POT_USVERTICAL"))
    )
    (comp (ref "R66")
      (value "100k")
      (footprint "eagle-import:R0603")
      (libsource (lib "eagle-import") (part "R-US_R0603"))
    )
    (comp (ref "R67")
      (value "4.30k")
      (footprint "eagle-import:R0603")
      (libsource (lib "eagle-import") (part "R-US_R0603"))
    )
    (comp (ref "R68")
      (value "4.30k")
      (footprint "eagle-import:R0603")
      (libsource (lib "eagle-import") (part "R-US_R0603"))
    )
    (comp (ref "R69")
      (value "100k")
      (footprint "eagle-import:R0603")
      (libsource (lib "eagle-import") (part "R-US_R0603"))
    )
    (comp (ref "R70")
      (value "3.90k")
      (footprint "eagle-import:R0603")
      (libsource (lib "eagle-import") (part "R-US_R0603"))
    )
    (comp (ref "R71")
      (value "100k")
      (footprint "eagle-import:R0603")
      (libsource (lib "eagle-import") (part "R-US_R0603"))
    )
    (comp (ref "R72")
      (value "1.0M")
      (footprint "eagle-import:R0603")
      (libsource (lib "eagle-import") (part "R-US_R0603"))
    )
    (comp (ref "R73")
      (value "4.30k")
      (footprint "eagle-import:R0603")
      (libsource (lib "eagle-import") (part "R-US_R0603"))
    )
    (comp (ref "R74")
      (value "66.50k")
      (footprint "eagle-import:R0603")
      (libsource (lib "eagle-import") (part "R-US_R0603"))
    )
    (comp (ref "R75")
      (value "1.2k")
      (footprint "eagle-import:R0603")
      (libsource (lib "eagle-import") (part "R-US_R0603"))
    )
    (comp (ref "R76")
      (value "100.0k")
      (footprint "eagle-import:R0603")
      (libsource (lib "eagle-import") (part "R-US_R0603"))
    )
    (comp (ref "R77")
      (value "1.0M")
      (footprint "eagle-import:R0603")
      (libsource (lib "eagle-import") (part "R-US_R0603"))
    )
    (comp (ref "R78")
      (value "100.0k")
      (footprint "eagle-import:R0603")
      (libsource (lib "eagle-import") (part "R-US_R0603"))
    )
    (comp (ref "R79")
      (value "100.0k")
      (footprint "eagle-import:R0603")
      (libsource (lib "eagle-import") (part "R-US_R0603"))
    )
    (comp (ref "R80")
      (value "1.2k")
      (footprint "eagle-import:R0603")
      (libsource (lib "eagle-import") (part "R-US_R0603"))
    )
    (comp (ref "R81")
      (value "1.0M")
      (footprint "eagle-import:R0603")
      (libsource (lib "eagle-import") (part "R-US_R0603"))
    )
    (comp (ref "R82")
      (value "66.50k")
      (footprint "eagle-import:R0603")
      (libsource (lib "eagle-import") (part "R-US_R0603"))
    )
    (comp (ref "R83")
      (value "33.20k")
      (footprint "eagle-import:R0603")
      (libsource (lib "eagle-import") (part "R-US_R0603"))
    )
    (comp (ref "R84")
      (value "402")
      (footprint "eagle-import:R0603")
      (libsource (lib "eagle-import") (part "R-US_R0603"))
    )
    (comp (ref "R85")
      (value "1.0M")
      (footprint "eagle-import:R0603")
      (libsource (lib "eagle-import") (part "R-US_R0603"))
    )
    (comp (ref "R87")
      (value "510")
      (footprint "eagle-import:R0603")
      (libsource (lib "eagle-import") (part "R-US_R0603"))
    )
    (comp (ref "R88")
      (value "510")
      (footprint "eagle-import:R0603")
      (libsource (lib "eagle-import") (part "R-US_R0603"))
    )
    (comp (ref "R89")
      (value "100.0k")
      (footprint "eagle-import:R0603")
      (libsource (lib "eagle-import") (part "R-US_R0603"))
    )
    (comp (ref "R90")
      (value "33.20k")
      (footprint "eagle-import:R0603")
      (libsource (lib "eagle-import") (part "R-US_R0603"))
    )
  )
  (nets
    (net (code "1") (name "1_TO_2") (class "Default")
      (node (ref "IC1") (pin "14") (pinfunction "OUT_14") (pintype "output"))
      (node (ref "R56") (pin "2") (pinfunction "2_2") (pintype "passive"))
      (node (ref "R8") (pin "1") (pinfunction "1_1") (pintype "passive"))
    )
    (net (code "2") (name "2_TO_3") (class "Default")
      (node (ref "IC4") (pin "14") (pinfunction "OUT_14") (pintype "output"))
      (node (ref "R41") (pin "1") (pinfunction "1_1") (pintype "passive"))
      (node (ref "R82") (pin "2") (pinfunction "2_2") (pintype "passive"))
    )
    (net (code "3") (name "3_TO_4") (class "Default")
      (node (ref "IC8") (pin "14") (pinfunction "OUT_14") (pintype "output"))
      (node (ref "R114") (pin "2") (pinfunction "2_2") (pintype "passive"))
      (node (ref "R68") (pin "1") (pinfunction "1_1") (pintype "passive"))
    )
    (net (code "4") (name "AREF_+10") (class "Default")
      (node (ref "C26") (pin "1") (pinfunction "1_1") (pintype "passive"))
      (node (ref "C28") (pin "1") (pinfunction "1_1") (pintype "passive"))
      (node (ref "C3") (pin "1") (pinfunction "1_1") (pintype "passive"))
      (node (ref "IC6") (pin "1") (pinfunction "C_1") (pintype "passive"))
      (node (ref "R1") (pin "2") (pinfunction "2_2") (pintype "passive"))
      (node (ref "R101") (pin "2") (pinfunction "2_2") (pintype "passive"))
      (node (ref "R117") (pin "2") (pinfunction "2_2") (pintype "passive"))
      (node (ref "R20") (pin "2") (pinfunction "2_2") (pintype "passive"))
      (node (ref "R3") (pin "1") (pinfunction "1_1") (pintype "passive"))
      (node (ref "R34") (pin "1") (pinfunction "1_1") (pintype "passive"))
      (node (ref "R38") (pin "2") (pinfunction "2_2") (pintype "passive"))
      (node (ref "R57") (pin "2") (pinfunction "2_2") (pintype "passive"))
      (node (ref "R59") (pin "2") (pinfunction "2_2") (pintype "passive"))
      (node (ref "R61") (pin "2") (pinfunction "2_2") (pintype "passive"))
      (node (ref "R63") (pin "1") (pinfunction "1_1") (pintype "passive"))
      (node (ref "R79") (pin "2") (pinfunction "2_2") (pintype "passive"))
      (node (ref "R95") (pin "1") (pinfunction "1_1") (pintype "passive"))
    )
    (net (code "5") (name "AREF_-10") (class "Default")
      (node (ref "C27") (pin "1") (pinfunction "1_1") (pintype "passive"))
      (node (ref "IC7") (pin "2") (pinfunction "A_2") (pintype "passive"))
      (node (ref "R109") (pin "2") (pinfunction "2_2") (pintype "passive"))
      (node (ref "R16") (pin "2") (pinfunction "2_2") (pintype "passive"))
      (node (ref "R28") (pin "2") (pinfunction "2_2") (pintype "passive"))
      (node (ref "R31") (pin "2") (pinfunction "2_2") (pintype "passive"))
      (node (ref "R49") (pin "2") (pinfunction "2_2") (pintype "passive"))
      (node (ref "R60") (pin "2") (pinfunction "2_2") (pintype "passive"))
      (node (ref "R76") (pin "2") (pinfunction "2_2") (pintype "passive"))
      (node (ref "R89") (pin "2") (pinfunction "2_2") (pintype "passive"))
      (node (ref "R92") (pin "2") (pinfunction "2_2") (pintype "passive"))
    )
    (net (code "6") (name "GND") (class "Default")
      (node (ref "C1") (pin "+") (pinfunction "+_+") (pintype "passive"))
      (node (ref "C11") (pin "2") (pinfunction "2_2") (pintype "passive"))
      (node (ref "C12") (pin "2") (pinfunction "2_2") (pintype "passive"))
      (node (ref "C13") (pin "2") (pinfunction "2_2") (pintype "passive"))
      (node (ref "C14") (pin "2") (pinfunction "2_2") (pintype "passive"))
      (node (ref "C15") (pin "2") (pinfunction "2_2") (pintype "passive"))
      (node (ref "C16") (pin "1") (pinfunction "1_1") (pintype "passive"))
      (node (ref "C17") (pin "1") (pinfunction "1_1") (pintype "passive"))
      (node (ref "C18") (pin "2") (pinfunction "2_2") (pintype "passive"))
      (node (ref "C2") (pin "-") (pinfunction "-_-") (pintype "passive"))
      (node (ref "C21") (pin "2") (pinfunction "2_2") (pintype "passive"))
      (node (ref "C22") (pin "1") (pinfunction "1_1") (pintype "passive"))
      (node (ref "C24") (pin "2") (pinfunction "2_2") (pintype "passive"))
      (node (ref "C25") (pin "2") (pinfunction "2_2") (pintype "passive"))
      (node (ref "C26") (pin "2") (pinfunction "2_2") (pintype "passive"))
      (node (ref "C27") (pin "2") (pinfunction "2_2") (pintype "passive"))
      (node (ref "C28") (pin "2") (pinfunction "2_2") (pintype "passive"))
      (node (ref "C29") (pin "1") (pinfunction "1_1") (pintype "passive"))
      (node (ref "C3") (pin "2") (pinfunction "2_2") (pintype "passive"))
      (node (ref "C30") (pin "2") (pinfunction "2_2") (pintype "passive"))
      (node (ref "C32") (pin "2") (pinfunction "2_2") (pintype "passive"))
      (node (ref "C33") (pin "1") (pinfunction "1_1") (pintype "passive"))
      (node (ref "C36") (pin "2") (pinfunction "2_2") (pintype "passive"))
      (node (ref "C37") (pin "2") (pinfunction "2_2") (pintype "passive"))
      (node (ref "C38") (pin "2") (pinfunction "2_2") (pintype "passive"))
      (node (ref "C39") (pin "2") (pinfunction "2_2") (pintype "passive"))
      (node (ref "C4") (pin "1") (pinfunction "1_1") (pintype "passive"))
      (node (ref "C40") (pin "2") (pinfunction "2_2") (pintype "passive"))
      (node (ref "C41") (pin "1") (pinfunction "1_1") (pintype "passive"))
      (node (ref "C42") (pin "1") (pinfunction "1_1") (pintype "passive"))
      (node (ref "C43") (pin "2") (pinfunction "2_2") (pintype "passive"))
      (node (ref "C46") (pin "2") (pinfunction "2_2") (pintype "passive"))
      (node (ref "C47") (pin "1") (pinfunction "1_1") (pintype "passive"))
      (node (ref "C5") (pin "2") (pinfunction "2_2") (pintype "passive"))
      (node (ref "C7") (pin "2") (pinfunction "2_2") (pintype "passive"))
      (node (ref "C8") (pin "1") (pinfunction "1_1") (pintype "passive"))
      (node (ref "D1") (pin "C") (pinfunction "C_C") (pintype "passive"))
      (node (ref "IC1") (pin "12") (pinfunction "+IN_12") (pintype "input"))
      (node (ref "IC1") (pin "3") (pinfunction "+IN_3") (pintype "input"))
      (node (ref "IC1") (pin "5") (pinfunction "+IN_5") (pintype "input"))
      (node (ref "IC10") (pin "8") (pinfunction "GND_8") (pintype "power_in"))
      (node (ref "IC11") (pin "12") (pinfunction "+IN_12") (pintype "input"))
      (node (ref "IC11") (pin "3") (pinfunction "+IN_3") (pintype "input"))
      (node (ref "IC11") (pin "5") (pinfunction "+IN_5") (pintype "input"))
      (node (ref "IC12") (pin "12") (pinfunction "+IN_12") (pintype "input"))
      (node (ref "IC12") (pin "3") (pinfunction "+IN_3") (pintype "input"))
      (node (ref "IC12") (pin "5") (pinfunction "+IN_5") (pintype "input"))
      (node (ref "IC2") (pin "12") (pinfunction "+IN_12") (pintype "input"))
      (node (ref "IC2") (pin "3") (pinfunction "+IN_3") (pintype "input"))
      (node (ref "IC2") (pin "5") (pinfunction "+IN_5") (pintype "input"))
      (node (ref "IC3") (pin "8") (pinfunction "GND_8") (pintype "power_in"))
      (node (ref "IC4") (pin "12") (pinfunction "+IN_12") (pintype "input"))
      (node (ref "IC4") (pin "3") (pinfunction "+IN_3") (pintype "input"))
      (node (ref "IC4") (pin "5") (pinfunction "+IN_5") (pintype "input"))
      (node (ref "IC5") (pin "12") (pinfunction "+IN_12") (pintype "input"))
      (node (ref "IC5") (pin "3") (pinfunction "+IN_3") (pintype "input"))
      (node (ref "IC5") (pin "5") (pinfunction "+IN_5") (pintype "input"))
      (node (ref "IC6") (pin "2") (pinfunction "A_2") (pintype "passive"))
      (node (ref "IC7") (pin "1") (pinfunction "C_1") (pintype "passive"))
      (node (ref "IC8") (pin "12") (pinfunction "+IN_12") (pintype "input"))
      (node (ref "IC8") (pin "3") (pinfunction "+IN_3") (pintype "input"))
      (node (ref "IC8") (pin "5") (pinfunction "+IN_5") (pintype "input"))
      (node (ref "IC9") (pin "12") (pinfunction "+IN_12") (pintype "input"))
      (node (ref "IC9") (pin "3") (pinfunction "+IN_3") (pintype "input"))
      (node (ref "IC9") (pin "5") (pinfunction "+IN_5") (pintype "input"))
      (node (ref "J1") (pin "P1") (pinfunction "1_P1") (pintype "passive"))
      (node (ref "J10") (pin "P1") (pinfunction "1_P1") (pintype "passive"))
      (node (ref "J11") (pin "P1") (pinfunction "1_P1") (pintype "passive"))
      (node (ref "J12") (pin "P1") (pinfunction "1_P1") (pintype "passive"))
      (node (ref "J12") (pin "P2") (pinfunction "2_P2") (pintype "passive"))
      (node (ref "J2") (pin "P1") (pinfunction "1_P1") (pintype "passive"))
      (node (ref "J3") (pin "P1") (pinfunction "1_P1") (pintype "passive"))
      (node (ref "J3") (pin "P2") (pinfunction "2_P2") (pintype "passive"))
      (node (ref "J4") (pin "P1") (pinfunction "1_P1") (pintype "passive"))
      (node (ref "J5") (pin "P1") (pinfunction "1_P1") (pintype "passive"))
      (node (ref "J6") (pin "P1") (pinfunction "1_P1") (pintype "passive"))
      (node (ref "J6") (pin "P2") (pinfunction "2_P2") (pintype "passive"))
      (node (ref "J7") (pin "P1") (pinfunction "1_P1") (pintype "passive"))
      (node (ref "J8") (pin "P1") (pinfunction "1_P1") (pintype "passive"))
      (node (ref "J9") (pin "P1") (pinfunction "1_P1") (pintype "passive"))
      (node (ref "J9") (pin "P2") (pinfunction "2_P2") (pintype "passive"))
      (node (ref "JP5") (pin "3") (pinfunction "3_3") (pintype "passive"))
      (node (ref "JP5") (pin "4") (pinfunction "4_4") (pintype "passive"))
      (node (ref "JP5") (pin "5") (pinfunction "5_5") (pintype "passive"))
      (node (ref "JP5") (pin "6") (pinfunction "6_6") (pintype "passive"))
      (node (ref "JP5") (pin "7") (pinfunction "7_7") (pintype "passive"))
      (node (ref "JP5") (pin "8") (pinfunction "8_8") (pintype "passive"))
      (node (ref "R108") (pin "2") (pinfunction "2_2") (pintype "passive"))
      (node (ref "R110") (pin "2") (pinfunction "2_2") (pintype "passive"))
      (node (ref "R113") (pin "2") (pinfunction "2_2") (pintype "passive"))
      (node (ref "R12") (pin "2") (pinfunction "2_2") (pintype "passive"))
      (node (ref "R15") (pin "2") (pinfunction "2_2") (pintype "passive"))
      (node (ref "R18") (pin "2") (pinfunction "2_2") (pintype "passive"))
      (node (ref "R21") (pin "2") (pinfunction "2_2") (pintype "passive"))
      (node (ref "R35") (pin "2") (pinfunction "2_2") (pintype "passive"))
      (node (ref "R36") (pin "P$3") (pinfunction "A_P$3") (pintype "passive"))
      (node (ref "R4") (pin "P$3") (pinfunction "A_P$3") (pintype "passive"))
      (node (ref "R48") (pin "2") (pinfunction "2_2") (pintype "passive"))
      (node (ref "R52") (pin "2") (pinfunction "2_2") (pintype "passive"))
      (node (ref "R53") (pin "2") (pinfunction "2_2") (pintype "passive"))
      (node (ref "R64") (pin "P$3") (pinfunction "A_P$3") (pintype "passive"))
      (node (ref "R72") (pin "2") (pinfunction "2_2") (pintype "passive"))
      (node (ref "R75") (pin "2") (pinfunction "2_2") (pintype "passive"))
      (node (ref "R77") (pin "2") (pinfunction "2_2") (pintype "passive"))
      (node (ref "R80") (pin "2") (pinfunction "2_2") (pintype "passive"))
      (node (ref "R96") (pin "2") (pinfunction "2_2") (pintype "passive"))
      (node (ref "R97") (pin "P$3") (pinfunction "A_P$3") (pintype "passive"))
    )
    (net (code "7") (name "Net-(C12-Pad1)") (class "Default")
      (node (ref "C12") (pin "1") (pinfunction "1_1") (pintype "passive"))
      (node (ref "R26") (pin "1") (pinfunction "1_1") (pintype "passive"))
    )
    (net (code "8") (name "Net-(C13-Pad1)") (class "Default")
      (node (ref "C13") (pin "1") (pinfunction "1_1") (pintype "passive"))
      (node (ref "R27") (pin "1") (pinfunction "1_1") (pintype "passive"))
    )
    (net (code "9") (name "Net-(C14-Pad1)") (class "Default")
      (node (ref "C14") (pin "1") (pinfunction "1_1") (pintype "passive"))
      (node (ref "R33") (pin "1") (pinfunction "1_1") (pintype "passive"))
    )
    (net (code "10") (name "Net-(C15-Pad1)") (class "Default")
      (node (ref "C15") (pin "1") (pinfunction "1_1") (pintype "passive"))
      (node (ref "R32") (pin "1") (pinfunction "1_1") (pintype "passive"))
    )
    (net (code "11") (name "Net-(C37-Pad1)") (class "Default")
      (node (ref "C37") (pin "1") (pinfunction "1_1") (pintype "passive"))
      (node (ref "R87") (pin "1") (pinfunction "1_1") (pintype "passive"))
    )
    (net (code "12") (name "Net-(C38-Pad1)") (class "Default")
      (node (ref "C38") (pin "1") (pinfunction "1_1") (pintype "passive"))
      (node (ref "R88") (pin "1") (pinfunction "1_1") (pintype "passive"))
    )
    (net (code "13") (name "Net-(C39-Pad1)") (class "Default")
      (node (ref "C39") (pin "1") (pinfunction "1_1") (pintype "passive"))
      (node (ref "R94") (pin "1") (pinfunction "1_1") (pintype "passive"))
    )
    (net (code "14") (name "Net-(C40-Pad1)") (class "Default")
      (node (ref "C40") (pin "1") (pinfunction "1_1") (pintype "passive"))
      (node (ref "R93") (pin "1") (pinfunction "1_1") (pintype "passive"))
    )
    (net (code "15") (name "Net-(D2-PadA)") (class "Default")
      (node (ref "D2") (pin "A") (pinfunction "A_A") (pintype "passive"))
      (node (ref "JP5") (pin "1") (pinfunction "1_1") (pintype "passive"))
      (node (ref "JP5") (pin "2") (pinfunction "2_2") (pintype "passive"))
    )
    (net (code "16") (name "Net-(D2-PadC)") (class "Default")
      (node (ref "D2") (pin "C") (pinfunction "C_C") (pintype "passive"))
      (node (ref "L1") (pin "2") (pinfunction "2_2") (pintype "passive"))
    )
    (net (code "17") (name "Net-(IC1A--IN)") (class "Default")
      (node (ref "IC1") (pin "2") (pinfunction "-IN_2") (pintype "input"))
      (node (ref "IC3") (pin "13") (pinfunction "OUT_13") (pintype "output"))
      (node (ref "R7") (pin "2") (pinfunction "2_2") (pintype "passive"))
    )
    (net (code "18") (name "Net-(IC1A-OUT)") (class "Default")
      (node (ref "IC1") (pin "1") (pinfunction "OUT_1") (pintype "output"))
      (node (ref "R13") (pin "2") (pinfunction "2_2") (pintype "passive"))
      (node (ref "R7") (pin "1") (pinfunction "1_1") (pintype "passive"))
    )
    (net (code "19") (name "Net-(IC1B--IN)") (class "Default")
      (node (ref "C9") (pin "1") (pinfunction "1_1") (pintype "passive"))
      (node (ref "IC1") (pin "6") (pinfunction "-IN_6") (pintype "input"))
      (node (ref "R13") (pin "1") (pinfunction "1_1") (pintype "passive"))
      (node (ref "R14") (pin "2") (pinfunction "2_2") (pintype "passive"))
      (node (ref "R23") (pin "1") (pinfunction "1_1") (pintype "passive"))
    )
    (net (code "20") (name "Net-(IC1B-OUT)") (class "Default")
      (node (ref "C9") (pin "2") (pinfunction "2_2") (pintype "passive"))
      (node (ref "IC1") (pin "7") (pinfunction "OUT_7") (pintype "output"))
      (node (ref "R14") (pin "1") (pinfunction "1_1") (pintype "passive"))
      (node (ref "R17") (pin "2") (pinfunction "2_2") (pintype "passive"))
      (node (ref "R24") (pin "2") (pinfunction "2_2") (pintype "passive"))
    )
    (net (code "21") (name "Net-(IC1C-+IN)") (class "Default")
      (node (ref "IC1") (pin "10") (pinfunction "+IN_10") (pintype "input"))
      (node (ref "R18") (pin "1") (pinfunction "1_1") (pintype "passive"))
      (node (ref "R24") (pin "1") (pinfunction "1_1") (pintype "passive"))
    )
    (net (code "22") (name "Net-(IC1C--IN)") (class "Default")
      (node (ref "IC1") (pin "9") (pinfunction "-IN_9") (pintype "input"))
      (node (ref "LED1") (pin "A") (pinfunction "A_A") (pintype "passive"))
      (node (ref "R15") (pin "1") (pinfunction "1_1") (pintype "passive"))
    )
    (net (code "23") (name "Net-(IC1C-OUT)") (class "Default")
      (node (ref "IC1") (pin "8") (pinfunction "OUT_8") (pintype "output"))
      (node (ref "LED1") (pin "K") (pinfunction "C_K") (pintype "passive"))
    )
    (net (code "24") (name "Net-(IC1D--IN)") (class "Default")
      (node (ref "IC1") (pin "13") (pinfunction "-IN_13") (pintype "input"))
      (node (ref "R10") (pin "1") (pinfunction "1_1") (pintype "passive"))
      (node (ref "R8") (pin "2") (pinfunction "2_2") (pintype "passive"))
    )
    (net (code "25") (name "Net-(IC2A--IN)") (class "Default")
      (node (ref "C6") (pin "2") (pinfunction "2_2") (pintype "passive"))
      (node (ref "IC2") (pin "2") (pinfunction "-IN_2") (pintype "input"))
      (node (ref "R1") (pin "1") (pinfunction "1_1") (pintype "passive"))
      (node (ref "R2") (pin "1") (pinfunction "1_1") (pintype "passive"))
      (node (ref "R4") (pin "P$1") (pinfunction "E_P$1") (pintype "passive"))
      (node (ref "R5") (pin "P$3") (pinfunction "A_P$3") (pintype "passive"))
      (node (ref "R6") (pin "2") (pinfunction "2_2") (pintype "passive"))
    )
    (net (code "26") (name "Net-(IC2A-OUT)") (class "Default")
      (node (ref "C6") (pin "1") (pinfunction "1_1") (pintype "passive"))
      (node (ref "IC2") (pin "1") (pinfunction "OUT_1") (pintype "output"))
      (node (ref "R22") (pin "2") (pinfunction "2_2") (pintype "passive"))
      (node (ref "R23") (pin "2") (pinfunction "2_2") (pintype "passive"))
      (node (ref "R29") (pin "2") (pinfunction "2_2") (pintype "passive"))
      (node (ref "R6") (pin "1") (pinfunction "1_1") (pintype "passive"))
    )
    (net (code "27") (name "Net-(IC2B--IN)") (class "Default")
      (node (ref "C10") (pin "1") (pinfunction "1_1") (pintype "passive"))
      (node (ref "IC2") (pin "6") (pinfunction "-IN_6") (pintype "input"))
      (node (ref "IC3") (pin "4") (pinfunction "OUT_4") (pintype "output"))
      (node (ref "R19") (pin "1") (pinfunction "1_1") (pintype "passive"))
      (node (ref "R20") (pin "1") (pinfunction "1_1") (pintype "passive"))
    )
    (net (code "28") (name "Net-(IC2B-OUT)") (class "Default")
      (node (ref "C10") (pin "2") (pinfunction "2_2") (pintype "passive"))
      (node (ref "IC2") (pin "7") (pinfunction "OUT_7") (pintype "output"))
      (node (ref "IC3") (pin "14") (pinfunction "CTRL_14") (pintype "input"))
      (node (ref "IC3") (pin "3") (pinfunction "CTRL_3") (pintype "input"))
    )
    (net (code "29") (name "Net-(IC2C-+IN)") (class "Default")
      (node (ref "IC2") (pin "10") (pinfunction "+IN_10") (pintype "input"))
      (node (ref "R12") (pin "1") (pinfunction "1_1") (pintype "passive"))
      (node (ref "R22") (pin "1") (pinfunction "1_1") (pintype "passive"))
    )
    (net (code "30") (name "Net-(IC2C--IN)") (class "Default")
      (node (ref "IC2") (pin "9") (pinfunction "-IN_9") (pintype "input"))
      (node (ref "LED2") (pin "A") (pinfunction "A_A") (pintype "passive"))
      (node (ref "R21") (pin "1") (pinfunction "1_1") (pintype "passive"))
    )
    (net (code "31") (name "Net-(IC2C-OUT)") (class "Default")
      (node (ref "IC2") (pin "8") (pinfunction "OUT_8") (pintype "output"))
      (node (ref "LED2") (pin "K") (pinfunction "C_K") (pintype "passive"))
    )
    (net (code "32") (name "Net-(IC2D--IN)") (class "Default")
      (node (ref "IC2") (pin "13") (pinfunction "-IN_13") (pintype "input"))
      (node (ref "R5") (pin "P$1") (pinfunction "E_P$1") (pintype "passive"))
      (node (ref "R9") (pin "2") (pinfunction "2_2") (pintype "passive"))
    )
    (net (code "33") (name "Net-(IC2D-OUT)") (class "Default")
      (node (ref "IC2") (pin "14") (pinfunction "OUT_14") (pintype "output"))
      (node (ref "R2") (pin "2") (pinfunction "2_2") (pintype "passive"))
      (node (ref "R9") (pin "1") (pinfunction "1_1") (pintype "passive"))
    )
    (net (code "34") (name "Net-(IC3A-IN)") (class "Default")
      (node (ref "IC3") (pin "2") (pinfunction "IN_2") (pintype "input"))
      (node (ref "R27") (pin "2") (pinfunction "2_2") (pintype "passive"))
      (node (ref "R28") (pin "1") (pinfunction "1_1") (pintype "passive"))
    )
    (net (code "35") (name "Net-(IC3B-CTRL)") (class "Default")
      (node (ref "C19") (pin "2") (pinfunction "2_2") (pintype "passive"))
      (node (ref "IC3") (pin "11") (pinfunction "CTRL_11") (pintype "input"))
      (node (ref "IC3") (pin "6") (pinfunction "CTRL_6") (pintype "input"))
      (node (ref "IC5") (pin "1") (pinfunction "OUT_1") (pintype "output"))
    )
    (net (code "36") (name "Net-(IC3B-IN)") (class "Default")
      (node (ref "IC3") (pin "7") (pinfunction "IN_7") (pintype "input"))
      (node (ref "R31") (pin "1") (pinfunction "1_1") (pintype "passive"))
      (node (ref "R33") (pin "2") (pinfunction "2_2") (pintype "passive"))
    )
    (net (code "37") (name "Net-(IC3B-OUT)") (class "Default")
      (node (ref "C19") (pin "1") (pinfunction "1_1") (pintype "passive"))
      (node (ref "IC3") (pin "5") (pinfunction "OUT_5") (pintype "output"))
      (node (ref "IC5") (pin "2") (pinfunction "-IN_2") (pintype "input"))
      (node (ref "R38") (pin "1") (pinfunction "1_1") (pintype "passive"))
      (node (ref "R39") (pin "1") (pinfunction "1_1") (pintype "passive"))
    )
    (net (code "38") (name "Net-(IC3C-IN)") (class "Default")
      (node (ref "IC3") (pin "10") (pinfunction "IN_10") (pintype "input"))
      (node (ref "R30") (pin "1") (pinfunction "1_1") (pintype "passive"))
      (node (ref "R32") (pin "2") (pinfunction "2_2") (pintype "passive"))
    )
    (net (code "39") (name "Net-(IC3C-OUT)") (class "Default")
      (node (ref "IC3") (pin "12") (pinfunction "OUT_12") (pintype "output"))
      (node (ref "IC4") (pin "2") (pinfunction "-IN_2") (pintype "input"))
      (node (ref "R40") (pin "2") (pinfunction "2_2") (pintype "passive"))
    )
    (net (code "40") (name "Net-(IC3D-IN)") (class "Default")
      (node (ref "IC3") (pin "15") (pinfunction "IN_15") (pintype "input"))
      (node (ref "R26") (pin "2") (pinfunction "2_2") (pintype "passive"))
      (node (ref "R29") (pin "1") (pinfunction "1_1") (pintype "passive"))
    )
    (net (code "41") (name "Net-(IC3E-MODE)") (class "Default")
      (node (ref "IC3") (pin "1") (pinfunction "MODE_1") (pintype "input"))
      (node (ref "R25") (pin "2") (pinfunction "2_2") (pintype "passive"))
    )
    (net (code "42") (name "Net-(IC4A-OUT)") (class "Default")
      (node (ref "IC4") (pin "1") (pinfunction "OUT_1") (pintype "output"))
      (node (ref "R40") (pin "1") (pinfunction "1_1") (pintype "passive"))
      (node (ref "R46") (pin "2") (pinfunction "2_2") (pintype "passive"))
    )
    (net (code "43") (name "Net-(IC4B--IN)") (class "Default")
      (node (ref "C20") (pin "1") (pinfunction "1_1") (pintype "passive"))
      (node (ref "IC4") (pin "6") (pinfunction "-IN_6") (pintype "input"))
      (node (ref "R46") (pin "1") (pinfunction "1_1") (pintype "passive"))
      (node (ref "R47") (pin "2") (pinfunction "2_2") (pintype "passive"))
      (node (ref "R54") (pin "1") (pinfunction "1_1") (pintype "passive"))
      (node (ref "R56") (pin "1") (pinfunction "1_1") (pintype "passive"))
    )
    (net (code "44") (name "Net-(IC4B-OUT)") (class "Default")
      (node (ref "C20") (pin "2") (pinfunction "2_2") (pintype "passive"))
      (node (ref "IC4") (pin "7") (pinfunction "OUT_7") (pintype "output"))
      (node (ref "R47") (pin "1") (pinfunction "1_1") (pintype "passive"))
      (node (ref "R55") (pin "2") (pinfunction "2_2") (pintype "passive"))
      (node (ref "R58") (pin "2") (pinfunction "2_2") (pintype "passive"))
    )
    (net (code "45") (name "Net-(IC4C-+IN)") (class "Default")
      (node (ref "IC4") (pin "10") (pinfunction "+IN_10") (pintype "input"))
      (node (ref "R52") (pin "1") (pinfunction "1_1") (pintype "passive"))
      (node (ref "R58") (pin "1") (pinfunction "1_1") (pintype "passive"))
    )
    (net (code "46") (name "Net-(IC4C--IN)") (class "Default")
      (node (ref "IC4") (pin "9") (pinfunction "-IN_9") (pintype "input"))
      (node (ref "LED3") (pin "A") (pinfunction "A_A") (pintype "passive"))
      (node (ref "R48") (pin "1") (pinfunction "1_1") (pintype "passive"))
    )
    (net (code "47") (name "Net-(IC4C-OUT)") (class "Default")
      (node (ref "IC4") (pin "8") (pinfunction "OUT_8") (pintype "output"))
      (node (ref "LED3") (pin "K") (pinfunction "C_K") (pintype "passive"))
    )
    (net (code "48") (name "Net-(IC4D--IN)") (class "Default")
      (node (ref "IC4") (pin "13") (pinfunction "-IN_13") (pintype "input"))
      (node (ref "R41") (pin "2") (pinfunction "2_2") (pintype "passive"))
      (node (ref "R44") (pin "1") (pinfunction "1_1") (pintype "passive"))
    )
    (net (code "49") (name "Net-(IC5B--IN)") (class "Default")
      (node (ref "C23") (pin "2") (pinfunction "2_2") (pintype "passive"))
      (node (ref "IC5") (pin "6") (pinfunction "-IN_6") (pintype "input"))
      (node (ref "R36") (pin "P$1") (pinfunction "E_P$1") (pintype "passive"))
      (node (ref "R37") (pin "P$3") (pinfunction "A_P$3") (pintype "passive"))
      (node (ref "R50") (pin "1") (pinfunction "1_1") (pintype "passive"))
      (node (ref "R51") (pin "2") (pinfunction "2_2") (pintype "passive"))
      (node (ref "R57") (pin "1") (pinfunction "1_1") (pintype "passive"))
    )
    (net (code "50") (name "Net-(IC5B-OUT)") (class "Default")
      (node (ref "C23") (pin "1") (pinfunction "1_1") (pintype "passive"))
      (node (ref "IC5") (pin "7") (pinfunction "OUT_7") (pintype "output"))
      (node (ref "R30") (pin "2") (pinfunction "2_2") (pintype "passive"))
      (node (ref "R42") (pin "2") (pinfunction "2_2") (pintype "passive"))
      (node (ref "R51") (pin "1") (pinfunction "1_1") (pintype "passive"))
      (node (ref "R54") (pin "2") (pinfunction "2_2") (pintype "passive"))
    )
    (net (code "51") (name "Net-(IC5C-+IN)") (class "Default")
      (node (ref "IC5") (pin "10") (pinfunction "+IN_10") (pintype "input"))
      (node (ref "R35") (pin "1") (pinfunction "1_1") (pintype "passive"))
      (node (ref "R42") (pin "1") (pinfunction "1_1") (pintype "passive"))
    )
    (net (code "52") (name "Net-(IC5C--IN)") (class "Default")
      (node (ref "IC5") (pin "9") (pinfunction "-IN_9") (pintype "input"))
      (node (ref "LED4") (pin "A") (pinfunction "A_A") (pintype "passive"))
      (node (ref "R53") (pin "1") (pinfunction "1_1") (pintype "passive"))
    )
    (net (code "53") (name "Net-(IC5C-OUT)") (class "Default")
      (node (ref "IC5") (pin "8") (pinfunction "OUT_8") (pintype "output"))
      (node (ref "LED4") (pin "K") (pinfunction "C_K") (pintype "passive"))
    )
    (net (code "54") (name "Net-(IC5D--IN)") (class "Default")
      (node (ref "IC5") (pin "13") (pinfunction "-IN_13") (pintype "input"))
      (node (ref "R37") (pin "P$1") (pinfunction "E_P$1") (pintype "passive"))
      (node (ref "R43") (pin "2") (pinfunction "2_2") (pintype "passive"))
    )
    (net (code "55") (name "Net-(IC5D-OUT)") (class "Default")
      (node (ref "IC5") (pin "14") (pinfunction "OUT_14") (pintype "output"))
      (node (ref "R43") (pin "1") (pinfunction "1_1") (pintype "passive"))
      (node (ref "R50") (pin "2") (pinfunction "2_2") (pintype "passive"))
    )
    (net (code "56") (name "Net-(IC8A-OUT)") (class "Default")
      (node (ref "IC8") (pin "1") (pinfunction "OUT_1") (pintype "output"))
      (node (ref "R67") (pin "1") (pinfunction "1_1") (pintype "passive"))
      (node (ref "R73") (pin "2") (pinfunction "2_2") (pintype "passive"))
    )
    (net (code "57") (name "Net-(IC8B--IN)") (class "Default")
      (node (ref "C34") (pin "1") (pinfunction "1_1") (pintype "passive"))
      (node (ref "IC8") (pin "6") (pinfunction "-IN_6") (pintype "input"))
      (node (ref "R73") (pin "1") (pinfunction "1_1") (pintype "passive"))
      (node (ref "R74") (pin "2") (pinfunction "2_2") (pintype "passive"))
      (node (ref "R82") (pin "1") (pinfunction "1_1") (pintype "passive"))
      (node (ref "R83") (pin "1") (pinfunction "1_1") (pintype "passive"))
    )
    (net (code "58") (name "Net-(IC8B-OUT)") (class "Default")
      (node (ref "C34") (pin "2") (pinfunction "2_2") (pintype "passive"))
      (node (ref "IC8") (pin "7") (pinfunction "OUT_7") (pintype "output"))
      (node (ref "R74") (pin "1") (pinfunction "1_1") (pintype "passive"))
      (node (ref "R84") (pin "2") (pinfunction "2_2") (pintype "passive"))
      (node (ref "R85") (pin "2") (pinfunction "2_2") (pintype "passive"))
    )
    (net (code "59") (name "Net-(IC8C-+IN)") (class "Default")
      (node (ref "IC8") (pin "10") (pinfunction "+IN_10") (pintype "input"))
      (node (ref "R77") (pin "1") (pinfunction "1_1") (pintype "passive"))
      (node (ref "R85") (pin "1") (pinfunction "1_1") (pintype "passive"))
    )
    (net (code "60") (name "Net-(IC8C--IN)") (class "Default")
      (node (ref "IC8") (pin "9") (pinfunction "-IN_9") (pintype "input"))
      (node (ref "LED5") (pin "A") (pinfunction "A_A") (pintype "passive"))
      (node (ref "R75") (pin "1") (pinfunction "1_1") (pintype "passive"))
    )
    (net (code "61") (name "Net-(IC8C-OUT)") (class "Default")
      (node (ref "IC8") (pin "8") (pinfunction "OUT_8") (pintype "output"))
      (node (ref "LED5") (pin "K") (pinfunction "C_K") (pintype "passive"))
    )
    (net (code "62") (name "Net-(IC8D--IN)") (class "Default")
      (node (ref "IC8") (pin "13") (pinfunction "-IN_13") (pintype "input"))
      (node (ref "R68") (pin "2") (pinfunction "2_2") (pintype "passive"))
      (node (ref "R70") (pin "1") (pinfunction "1_1") (pintype "passive"))
    )
    (net (code "63") (name "Net-(IC9A--IN)") (class "Default")
      (node (ref "C31") (pin "2") (pinfunction "2_2") (pintype "passive"))
      (node (ref "IC9") (pin "2") (pinfunction "-IN_2") (pintype "input"))
      (node (ref "R61") (pin "1") (pinfunction "1_1") (pintype "passive"))
      (node (ref "R62") (pin "1") (pinfunction "1_1") (pintype "passive"))
      (node (ref "R64") (pin "P$1") (pinfunction "E_P$1") (pintype "passive"))
      (node (ref "R65") (pin "P$3") (pinfunction "A_P$3") (pintype "passive"))
      (node (ref "R66") (pin "2") (pinfunction "2_2") (pintype "passive"))
    )
    (net (code "64") (name "Net-(IC9A-OUT)") (class "Default")
      (node (ref "C31") (pin "1") (pinfunction "1_1") (pintype "passive"))
      (node (ref "IC9") (pin "1") (pinfunction "OUT_1") (pintype "output"))
      (node (ref "R66") (pin "1") (pinfunction "1_1") (pintype "passive"))
      (node (ref "R81") (pin "2") (pinfunction "2_2") (pintype "passive"))
      (node (ref "R83") (pin "2") (pinfunction "2_2") (pintype "passive"))
      (node (ref "R90") (pin "2") (pinfunction "2_2") (pintype "passive"))
    )
    (net (code "65") (name "Net-(IC9C-+IN)") (class "Default")
      (node (ref "IC9") (pin "10") (pinfunction "+IN_10") (pintype "input"))
      (node (ref "R72") (pin "1") (pinfunction "1_1") (pintype "passive"))
      (node (ref "R81") (pin "1") (pinfunction "1_1") (pintype "passive"))
    )
    (net (code "66") (name "Net-(IC9C--IN)") (class "Default")
      (node (ref "IC9") (pin "9") (pinfunction "-IN_9") (pintype "input"))
      (node (ref "LED6") (pin "A") (pinfunction "A_A") (pintype "passive"))
      (node (ref "R80") (pin "1") (pinfunction "1_1") (pintype "passive"))
    )
    (net (code "67") (name "Net-(IC9C-OUT)") (class "Default")
      (node (ref "IC9") (pin "8") (pinfunction "OUT_8") (pintype "output"))
      (node (ref "LED6") (pin "K") (pinfunction "C_K") (pintype "passive"))
    )
    (net (code "68") (name "Net-(IC9D--IN)") (class "Default")
      (node (ref "IC9") (pin "13") (pinfunction "-IN_13") (pintype "input"))
      (node (ref "R65") (pin "P$1") (pinfunction "E_P$1") (pintype "passive"))
      (node (ref "R69") (pin "2") (pinfunction "2_2") (pintype "passive"))
    )
    (net (code "69") (name "Net-(IC9D-OUT)") (class "Default")
      (node (ref "IC9") (pin "14") (pinfunction "OUT_14") (pintype "output"))
      (node (ref "R62") (pin "2") (pinfunction "2_2") (pintype "passive"))
      (node (ref "R69") (pin "1") (pinfunction "1_1") (pintype "passive"))
    )
    (net (code "70") (name "Net-(IC10A-CTRL)") (class "Default")
      (node (ref "C35") (pin "2") (pinfunction "2_2") (pintype "passive"))
      (node (ref "IC10") (pin "14") (pinfunction "CTRL_14") (pintype "input"))
      (node (ref "IC10") (pin "3") (pinfunction "CTRL_3") (pintype "input"))
      (node (ref "IC9") (pin "7") (pinfunction "OUT_7") (pintype "output"))
    )
    (net (code "71") (name "Net-(IC10A-IN)") (class "Default")
      (node (ref "IC10") (pin "2") (pinfunction "IN_2") (pintype "input"))
      (node (ref "R88") (pin "2") (pinfunction "2_2") (pintype "passive"))
      (node (ref "R89") (pin "1") (pinfunction "1_1") (pintype "passive"))
    )
    (net (code "72") (name "Net-(IC10A-OUT)") (class "Default")
      (node (ref "C35") (pin "1") (pinfunction "1_1") (pintype "passive"))
      (node (ref "IC10") (pin "4") (pinfunction "OUT_4") (pintype "output"))
      (node (ref "IC9") (pin "6") (pinfunction "-IN_6") (pintype "input"))
      (node (ref "R78") (pin "1") (pinfunction "1_1") (pintype "passive"))
      (node (ref "R79") (pin "1") (pinfunction "1_1") (pintype "passive"))
    )
    (net (code "73") (name "Net-(IC10B-CTRL)") (class "Default")
      (node (ref "C44") (pin "2") (pinfunction "2_2") (pintype "passive"))
      (node (ref "IC10") (pin "11") (pinfunction "CTRL_11") (pintype "input"))
      (node (ref "IC10") (pin "6") (pinfunction "CTRL_6") (pintype "input"))
      (node (ref "IC12") (pin "1") (pinfunction "OUT_1") (pintype "output"))
    )
    (net (code "74") (name "Net-(IC10B-IN)") (class "Default")
      (node (ref "IC10") (pin "7") (pinfunction "IN_7") (pintype "input"))
      (node (ref "R92") (pin "1") (pinfunction "1_1") (pintype "passive"))
      (node (ref "R94") (pin "2") (pinfunction "2_2") (pintype "passive"))
    )
    (net (code "75") (name "Net-(IC10B-OUT)") (class "Default")
      (node (ref "C44") (pin "1") (pinfunction "1_1") (pintype "passive"))
      (node (ref "IC10") (pin "5") (pinfunction "OUT_5") (pintype "output"))
      (node (ref "IC12") (pin "2") (pinfunction "-IN_2") (pintype "input"))
      (node (ref "R101") (pin "1") (pinfunction "1_1") (pintype "passive"))
      (node (ref "R102") (pin "1") (pinfunction "1_1") (pintype "passive"))
    )
    (net (code "76") (name "Net-(IC10C-IN)") (class "Default")
      (node (ref "IC10") (pin "10") (pinfunction "IN_10") (pintype "input"))
      (node (ref "R91") (pin "1") (pinfunction "1_1") (pintype "passive"))
      (node (ref "R93") (pin "2") (pinfunction "2_2") (pintype "passive"))
    )
    (net (code "77") (name "Net-(IC10C-OUT)") (class "Default")
      (node (ref "IC10") (pin "12") (pinfunction "OUT_12") (pintype "output"))
      (node (ref "IC11") (pin "2") (pinfunction "-IN_2") (pintype "input"))
      (node (ref "R100") (pin "2") (pinfunction "2_2") (pintype "passive"))
    )
    (net (code "78") (name "Net-(IC10D-IN)") (class "Default")
      (node (ref "IC10") (pin "15") (pinfunction "IN_15") (pintype "input"))
      (node (ref "R87") (pin "2") (pinfunction "2_2") (pintype "passive"))
      (node (ref "R90") (pin "1") (pinfunction "1_1") (pintype "passive"))
    )
    (net (code "79") (name "Net-(IC10D-OUT)") (class "Default")
      (node (ref "IC10") (pin "13") (pinfunction "OUT_13") (pintype "output"))
      (node (ref "IC8") (pin "2") (pinfunction "-IN_2") (pintype "input"))
      (node (ref "R67") (pin "2") (pinfunction "2_2") (pintype "passive"))
    )
    (net (code "80") (name "Net-(IC10E-MODE)") (class "Default")
      (node (ref "IC10") (pin "1") (pinfunction "MODE_1") (pintype "input"))
      (node (ref "R86") (pin "2") (pinfunction "2_2") (pintype "passive"))
    )
    (net (code "81") (name "Net-(IC11A-OUT)") (class "Default")
      (node (ref "IC11") (pin "1") (pinfunction "OUT_1") (pintype "output"))
      (node (ref "R100") (pin "1") (pinfunction "1_1") (pintype "passive"))
      (node (ref "R99") (pin "2") (pinfunction "2_2") (pintype "passive"))
    )
    (net (code "82") (name "Net-(IC11B--IN)") (class "Default")
      (node (ref "C45") (pin "1") (pinfunction "1_1") (pintype "passive"))
      (node (ref "IC11") (pin "6") (pinfunction "-IN_6") (pintype "input"))
      (node (ref "R103") (pin "1") (pinfunction "1_1") (pintype "passive"))
      (node (ref "R107") (pin "2") (pinfunction "2_2") (pintype "passive"))
      (node (ref "R114") (pin "1") (pinfunction "1_1") (pintype "passive"))
      (node (ref "R99") (pin "1") (pinfunction "1_1") (pintype "passive"))
    )
    (net (code "83") (name "Net-(IC11B-OUT)") (class "Default")
      (node (ref "C45") (pin "2") (pinfunction "2_2") (pintype "passive"))
      (node (ref "IC11") (pin "7") (pinfunction "OUT_7") (pintype "output"))
      (node (ref "R107") (pin "1") (pinfunction "1_1") (pintype "passive"))
      (node (ref "R115") (pin "2") (pinfunction "2_2") (pintype "passive"))
      (node (ref "R116") (pin "2") (pinfunction "2_2") (pintype "passive"))
    )
    (net (code "84") (name "Net-(IC11C-+IN)") (class "Default")
      (node (ref "IC11") (pin "10") (pinfunction "+IN_10") (pintype "input"))
      (node (ref "R110") (pin "1") (pinfunction "1_1") (pintype "passive"))
      (node (ref "R115") (pin "1") (pinfunction "1_1") (pintype "passive"))
    )
    (net (code "85") (name "Net-(IC11C--IN)") (class "Default")
      (node (ref "IC11") (pin "9") (pinfunction "-IN_9") (pintype "input"))
      (node (ref "LED7") (pin "A") (pinfunction "A_A") (pintype "passive"))
      (node (ref "R108") (pin "1") (pinfunction "1_1") (pintype "passive"))
    )
    (net (code "86") (name "Net-(IC11C-OUT)") (class "Default")
      (node (ref "IC11") (pin "8") (pinfunction "OUT_8") (pintype "output"))
      (node (ref "LED7") (pin "K") (pinfunction "C_K") (pintype "passive"))
    )
    (net (code "87") (name "Net-(IC11D--IN)") (class "Default")
      (node (ref "IC11") (pin "13") (pinfunction "-IN_13") (pintype "input"))
      (node (ref "IC11") (pin "14") (pinfunction "OUT_14") (pintype "output"))
    )
    (net (code "88") (name "Net-(IC12B--IN)") (class "Default")
      (node (ref "C48") (pin "2") (pinfunction "2_2") (pintype "passive"))
      (node (ref "IC12") (pin "6") (pinfunction "-IN_6") (pintype "input"))
      (node (ref "R111") (pin "1") (pinfunction "1_1") (pintype "passive"))
      (node (ref "R112") (pin "2") (pinfunction "2_2") (pintype "passive"))
      (node (ref "R117") (pin "1") (pinfunction "1_1") (pintype "passive"))
      (node (ref "R97") (pin "P$1") (pinfunction "E_P$1") (pintype "passive"))
      (node (ref "R98") (pin "P$3") (pinfunction "A_P$3") (pintype "passive"))
    )
    (net (code "89") (name "Net-(IC12B-OUT)") (class "Default")
      (node (ref "C48") (pin "1") (pinfunction "1_1") (pintype "passive"))
      (node (ref "IC12") (pin "7") (pinfunction "OUT_7") (pintype "output"))
      (node (ref "R103") (pin "2") (pinfunction "2_2") (pintype "passive"))
      (node (ref "R104") (pin "2") (pinfunction "2_2") (pintype "passive"))
      (node (ref "R112") (pin "1") (pinfunction "1_1") (pintype "passive"))
      (node (ref "R91") (pin "2") (pinfunction "2_2") (pintype "passive"))
    )
    (net (code "90") (name "Net-(IC12C-+IN)") (class "Default")
      (node (ref "IC12") (pin "10") (pinfunction "+IN_10") (pintype "input"))
      (node (ref "R104") (pin "1") (pinfunction "1_1") (pintype "passive"))
      (node (ref "R96") (pin "1") (pinfunction "1_1") (pintype "passive"))
    )
    (net (code "91") (name "Net-(IC12C--IN)") (class "Default")
      (node (ref "IC12") (pin "9") (pinfunction "-IN_9") (pintype "input"))
      (node (ref "LED8") (pin "A") (pinfunction "A_A") (pintype "passive"))
      (node (ref "R113") (pin "1") (pinfunction "1_1") (pintype "passive"))
    )
    (net (code "92") (name "Net-(IC12C-OUT)") (class "Default")
      (node (ref "IC12") (pin "8") (pinfunction "OUT_8") (pintype "output"))
      (node (ref "LED8") (pin "K") (pinfunction "C_K") (pintype "passive"))
    )
    (net (code "93") (name "Net-(IC12D--IN)") (class "Default")
      (node (ref "IC12") (pin "13") (pinfunction "-IN_13") (pintype "input"))
      (node (ref "R105") (pin "2") (pinfunction "2_2") (pintype "passive"))
      (node (ref "R98") (pin "P$1") (pinfunction "E_P$1") (pintype "passive"))
    )
    (net (code "94") (name "Net-(IC12D-OUT)") (class "Default")
      (node (ref "IC12") (pin "14") (pinfunction "OUT_14") (pintype "output"))
      (node (ref "R105") (pin "1") (pinfunction "1_1") (pintype "passive"))
      (node (ref "R111") (pin "2") (pinfunction "2_2") (pintype "passive"))
    )
    (net (code "95") (name "Net-(J1-2)") (class "Default")
      (node (ref "J1") (pin "P2") (pinfunction "2_P2") (pintype "passive"))
      (node (ref "R3") (pin "2") (pinfunction "2_2") (pintype "passive"))
    )
    (net (code "96") (name "Net-(J1-3)") (class "Default")
      (node (ref "J1") (pin "P3") (pinfunction "3_P3") (pintype "passive"))
      (node (ref "R19") (pin "2") (pinfunction "2_2") (pintype "passive"))
    )
    (net (code "97") (name "Net-(J2-2)") (class "Default")
      (node (ref "J2") (pin "P2") (pinfunction "2_P2") (pintype "passive"))
      (node (ref "R10") (pin "2") (pinfunction "2_2") (pintype "passive"))
    )
    (net (code "98") (name "Net-(J2-3)") (class "Default")
      (node (ref "J2") (pin "P3") (pinfunction "3_P3") (pintype "passive"))
      (node (ref "R17") (pin "1") (pinfunction "1_1") (pintype "passive"))
    )
    (net (code "99") (name "Net-(J3-3)") (class "Default")
      (node (ref "J3") (pin "P3") (pinfunction "3_P3") (pintype "passive"))
      (node (ref "R11") (pin "2") (pinfunction "2_2") (pintype "passive"))
    )
    (net (code "100") (name "Net-(J4-2)") (class "Default")
      (node (ref "J4") (pin "P2") (pinfunction "2_P2") (pintype "passive"))
      (node (ref "R34") (pin "2") (pinfunction "2_2") (pintype "passive"))
    )
    (net (code "101") (name "Net-(J4-3)") (class "Default")
      (node (ref "J4") (pin "P3") (pinfunction "3_P3") (pintype "passive"))
      (node (ref "R39") (pin "2") (pinfunction "2_2") (pintype "passive"))
    )
    (net (code "102") (name "Net-(J5-2)") (class "Default")
      (node (ref "J5") (pin "P2") (pinfunction "2_P2") (pintype "passive"))
      (node (ref "R44") (pin "2") (pinfunction "2_2") (pintype "passive"))
    )
    (net (code "103") (name "Net-(J5-3)") (class "Default")
      (node (ref "J5") (pin "P3") (pinfunction "3_P3") (pintype "passive"))
      (node (ref "R55") (pin "1") (pinfunction "1_1") (pintype "passive"))
    )
    (net (code "104") (name "Net-(J6-3)") (class "Default")
      (node (ref "J6") (pin "P3") (pinfunction "3_P3") (pintype "passive"))
      (node (ref "R45") (pin "2") (pinfunction "2_2") (pintype "passive"))
    )
    (net (code "105") (name "Net-(J7-2)") (class "Default")
      (node (ref "J7") (pin "P2") (pinfunction "2_P2") (pintype "passive"))
      (node (ref "R63") (pin "2") (pinfunction "2_2") (pintype "passive"))
    )
    (net (code "106") (name "Net-(J7-3)") (class "Default")
      (node (ref "J7") (pin "P3") (pinfunction "3_P3") (pintype "passive"))
      (node (ref "R78") (pin "2") (pinfunction "2_2") (pintype "passive"))
    )
    (net (code "107") (name "Net-(J8-2)") (class "Default")
      (node (ref "J8") (pin "P2") (pinfunction "2_P2") (pintype "passive"))
      (node (ref "R70") (pin "2") (pinfunction "2_2") (pintype "passive"))
    )
    (net (code "108") (name "Net-(J8-3)") (class "Default")
      (node (ref "J8") (pin "P3") (pinfunction "3_P3") (pintype "passive"))
      (node (ref "R84") (pin "1") (pinfunction "1_1") (pintype "passive"))
    )
    (net (code "109") (name "Net-(J9-3)") (class "Default")
      (node (ref "J9") (pin "P3") (pinfunction "3_P3") (pintype "passive"))
      (node (ref "R71") (pin "2") (pinfunction "2_2") (pintype "passive"))
    )
    (net (code "110") (name "Net-(J10-2)") (class "Default")
      (node (ref "J10") (pin "P2") (pinfunction "2_P2") (pintype "passive"))
      (node (ref "R95") (pin "2") (pinfunction "2_2") (pintype "passive"))
    )
    (net (code "111") (name "Net-(J10-3)") (class "Default")
      (node (ref "J10") (pin "P3") (pinfunction "3_P3") (pintype "passive"))
      (node (ref "R102") (pin "2") (pinfunction "2_2") (pintype "passive"))
    )
    (net (code "112") (name "Net-(J11-3)") (class "Default")
      (node (ref "J11") (pin "P3") (pinfunction "3_P3") (pintype "passive"))
      (node (ref "R116") (pin "1") (pinfunction "1_1") (pintype "passive"))
    )
    (net (code "113") (name "Net-(J12-3)") (class "Default")
      (node (ref "J12") (pin "P3") (pinfunction "3_P3") (pintype "passive"))
      (node (ref "R106") (pin "2") (pinfunction "2_2") (pintype "passive"))
    )
    (net (code "114") (name "Net-(JP5-Pad10)") (class "Default")
      (node (ref "JP5") (pin "10") (pinfunction "10_10") (pintype "passive"))
      (node (ref "JP5") (pin "9") (pinfunction "9_9") (pintype "passive"))
      (node (ref "P1") (pin "2") (pinfunction "2_2") (pintype "bidirectional"))
    )
    (net (code "115") (name "Net-(L2-Pad2)") (class "Default")
      (node (ref "L2") (pin "2") (pinfunction "2_2") (pintype "passive"))
      (node (ref "P1") (pin "1") (pinfunction "1_1") (pintype "bidirectional"))
    )
    (net (code "116") (name "Net-(R4-S)") (class "Default")
      (node (ref "R16") (pin "1") (pinfunction "1_1") (pintype "passive"))
      (node (ref "R4") (pin "P$2") (pinfunction "S_P$2") (pintype "passive"))
    )
    (net (code "117") (name "Net-(R5-S)") (class "Default")
      (node (ref "R11") (pin "1") (pinfunction "1_1") (pintype "passive"))
      (node (ref "R5") (pin "P$2") (pinfunction "S_P$2") (pintype "passive"))
    )
    (net (code "118") (name "Net-(R36-S)") (class "Default")
      (node (ref "R36") (pin "P$2") (pinfunction "S_P$2") (pintype "passive"))
      (node (ref "R49") (pin "1") (pinfunction "1_1") (pintype "passive"))
    )
    (net (code "119") (name "Net-(R37-S)") (class "Default")
      (node (ref "R37") (pin "P$2") (pinfunction "S_P$2") (pintype "passive"))
      (node (ref "R45") (pin "1") (pinfunction "1_1") (pintype "passive"))
    )
    (net (code "120") (name "Net-(R64-S)") (class "Default")
      (node (ref "R64") (pin "P$2") (pinfunction "S_P$2") (pintype "passive"))
      (node (ref "R76") (pin "1") (pinfunction "1_1") (pintype "passive"))
    )
    (net (code "121") (name "Net-(R65-S)") (class "Default")
      (node (ref "R65") (pin "P$2") (pinfunction "S_P$2") (pintype "passive"))
      (node (ref "R71") (pin "1") (pinfunction "1_1") (pintype "passive"))
    )
    (net (code "122") (name "Net-(R97-S)") (class "Default")
      (node (ref "R109") (pin "1") (pinfunction "1_1") (pintype "passive"))
      (node (ref "R97") (pin "P$2") (pinfunction "S_P$2") (pintype "passive"))
    )
    (net (code "123") (name "Net-(R98-S)") (class "Default")
      (node (ref "R106") (pin "1") (pinfunction "1_1") (pintype "passive"))
      (node (ref "R98") (pin "P$2") (pinfunction "S_P$2") (pintype "passive"))
    )
    (net (code "124") (name "VCC") (class "Default")
      (node (ref "C11") (pin "1") (pinfunction "1_1") (pintype "passive"))
      (node (ref "C18") (pin "1") (pinfunction "1_1") (pintype "passive"))
      (node (ref "C2") (pin "+") (pinfunction "+_+") (pintype "passive"))
      (node (ref "C21") (pin "1") (pinfunction "1_1") (pintype "passive"))
      (node (ref "C24") (pin "1") (pinfunction "1_1") (pintype "passive"))
      (node (ref "C30") (pin "1") (pinfunction "1_1") (pintype "passive"))
      (node (ref "C32") (pin "1") (pinfunction "1_1") (pintype "passive"))
      (node (ref "C36") (pin "1") (pinfunction "1_1") (pintype "passive"))
      (node (ref "C43") (pin "1") (pinfunction "1_1") (pintype "passive"))
      (node (ref "C46") (pin "1") (pinfunction "1_1") (pintype "passive"))
      (node (ref "C5") (pin "1") (pinfunction "1_1") (pintype "passive"))
      (node (ref "C7") (pin "1") (pinfunction "1_1") (pintype "passive"))
      (node (ref "IC1") (pin "4") (pinfunction "V+_4") (pintype "power_in"))
      (node (ref "IC10") (pin "16") (pinfunction "V+_16") (pintype "power_in"))
      (node (ref "IC11") (pin "4") (pinfunction "V+_4") (pintype "power_in"))
      (node (ref "IC12") (pin "4") (pinfunction "V+_4") (pintype "power_in"))
      (node (ref "IC2") (pin "4") (pinfunction "V+_4") (pintype "power_in"))
      (node (ref "IC3") (pin "16") (pinfunction "V+_16") (pintype "power_in"))
      (node (ref "IC4") (pin "4") (pinfunction "V+_4") (pintype "power_in"))
      (node (ref "IC5") (pin "4") (pinfunction "V+_4") (pintype "power_in"))
      (node (ref "IC8") (pin "4") (pinfunction "V+_4") (pintype "power_in"))
      (node (ref "IC9") (pin "4") (pinfunction "V+_4") (pintype "power_in"))
      (node (ref "L1") (pin "1") (pinfunction "1_1") (pintype "passive"))
      (node (ref "R25") (pin "1") (pinfunction "1_1") (pintype "passive"))
      (node (ref "R59") (pin "1") (pinfunction "1_1") (pintype "passive"))
      (node (ref "R86") (pin "1") (pinfunction "1_1") (pintype "passive"))
    )
    (net (code "125") (name "VEE") (class "Default")
      (node (ref "C1") (pin "-") (pinfunction "-_-") (pintype "passive"))
      (node (ref "C16") (pin "2") (pinfunction "2_2") (pintype "passive"))
      (node (ref "C17") (pin "2") (pinfunction "2_2") (pintype "passive"))
      (node (ref "C22") (pin "2") (pinfunction "2_2") (pintype "passive"))
      (node (ref "C25") (pin "1") (pinfunction "1_1") (pintype "passive"))
      (node (ref "C29") (pin "2") (pinfunction "2_2") (pintype "passive"))
      (node (ref "C33") (pin "2") (pinfunction "2_2") (pintype "passive"))
      (node (ref "C4") (pin "2") (pinfunction "2_2") (pintype "passive"))
      (node (ref "C41") (pin "2") (pinfunction "2_2") (pintype "passive"))
      (node (ref "C42") (pin "2") (pinfunction "2_2") (pintype "passive"))
      (node (ref "C47") (pin "2") (pinfunction "2_2") (pintype "passive"))
      (node (ref "C8") (pin "2") (pinfunction "2_2") (pintype "passive"))
      (node (ref "D1") (pin "A") (pinfunction "A_A") (pintype "passive"))
      (node (ref "IC1") (pin "11") (pinfunction "V-_11") (pintype "power_in"))
      (node (ref "IC10") (pin "9") (pinfunction "V-_9") (pintype "power_in"))
      (node (ref "IC11") (pin "11") (pinfunction "V-_11") (pintype "power_in"))
      (node (ref "IC12") (pin "11") (pinfunction "V-_11") (pintype "power_in"))
      (node (ref "IC2") (pin "11") (pinfunction "V-_11") (pintype "power_in"))
      (node (ref "IC3") (pin "9") (pinfunction "V-_9") (pintype "power_in"))
      (node (ref "IC4") (pin "11") (pinfunction "V-_11") (pintype "power_in"))
      (node (ref "IC5") (pin "11") (pinfunction "V-_11") (pintype "power_in"))
      (node (ref "IC8") (pin "11") (pinfunction "V-_11") (pintype "power_in"))
      (node (ref "IC9") (pin "11") (pinfunction "V-_11") (pintype "power_in"))
      (node (ref "L2") (pin "1") (pinfunction "1_1") (pintype "passive"))
      (node (ref "R60") (pin "1") (pinfunction "1_1") (pintype "passive"))
    )
    (net (code "126") (name "unconnected-(J11-2-PadP2)") (class "Default")
      (node (ref "J11") (pin "P2") (pinfunction "2_P2") (pintype "passive"))
    )
  )
)
